# mosfet_ctl.net
KiCad netlist of a schematic drawn in EAGLE
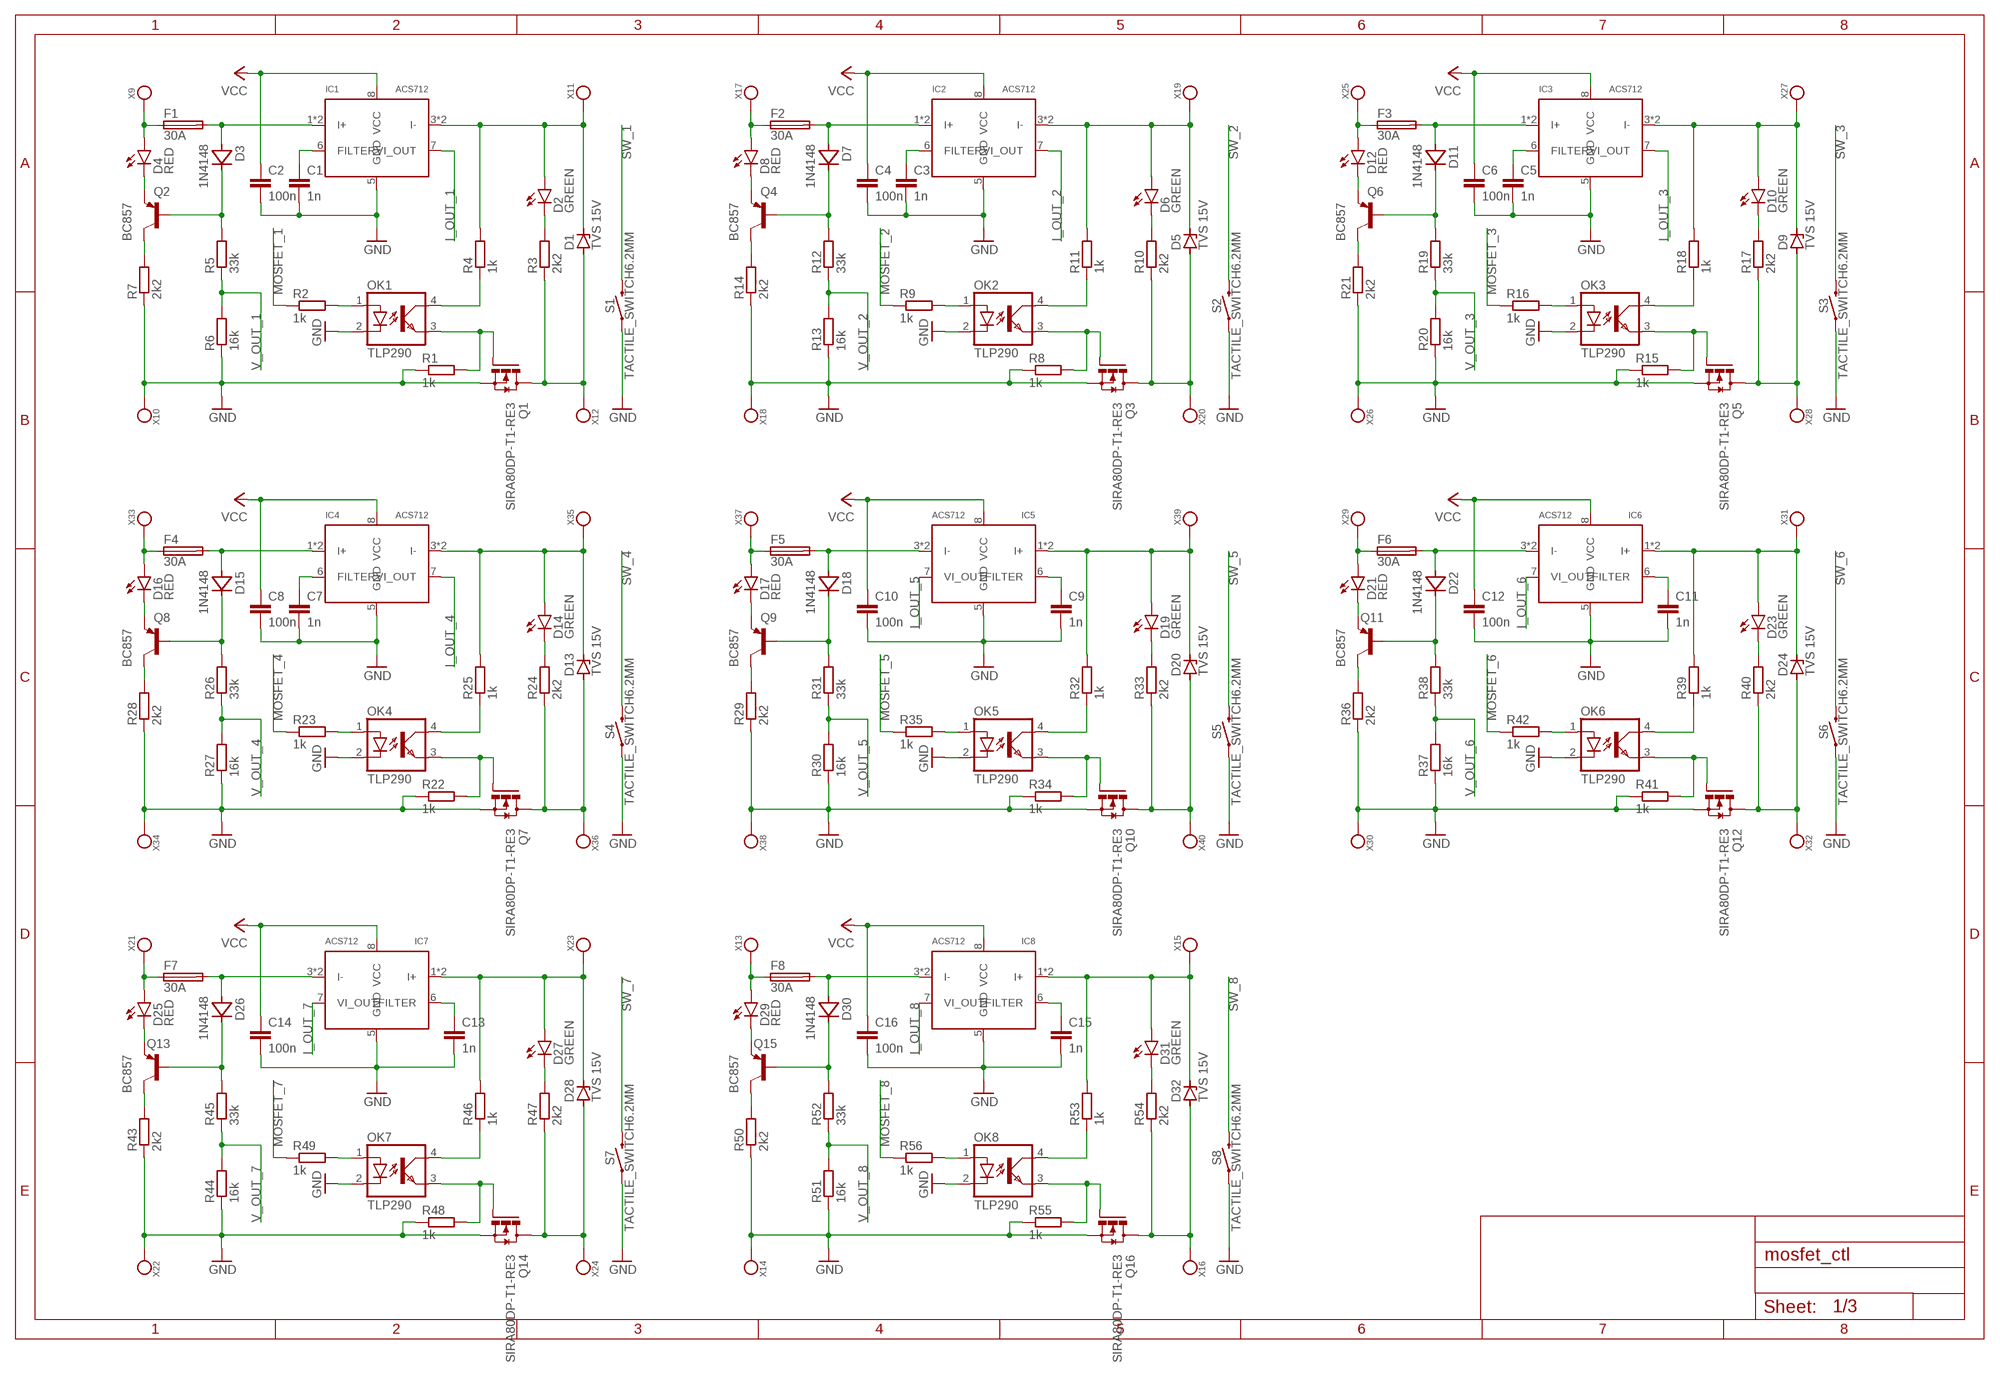
[diagram p0: schematic, sheet 1]
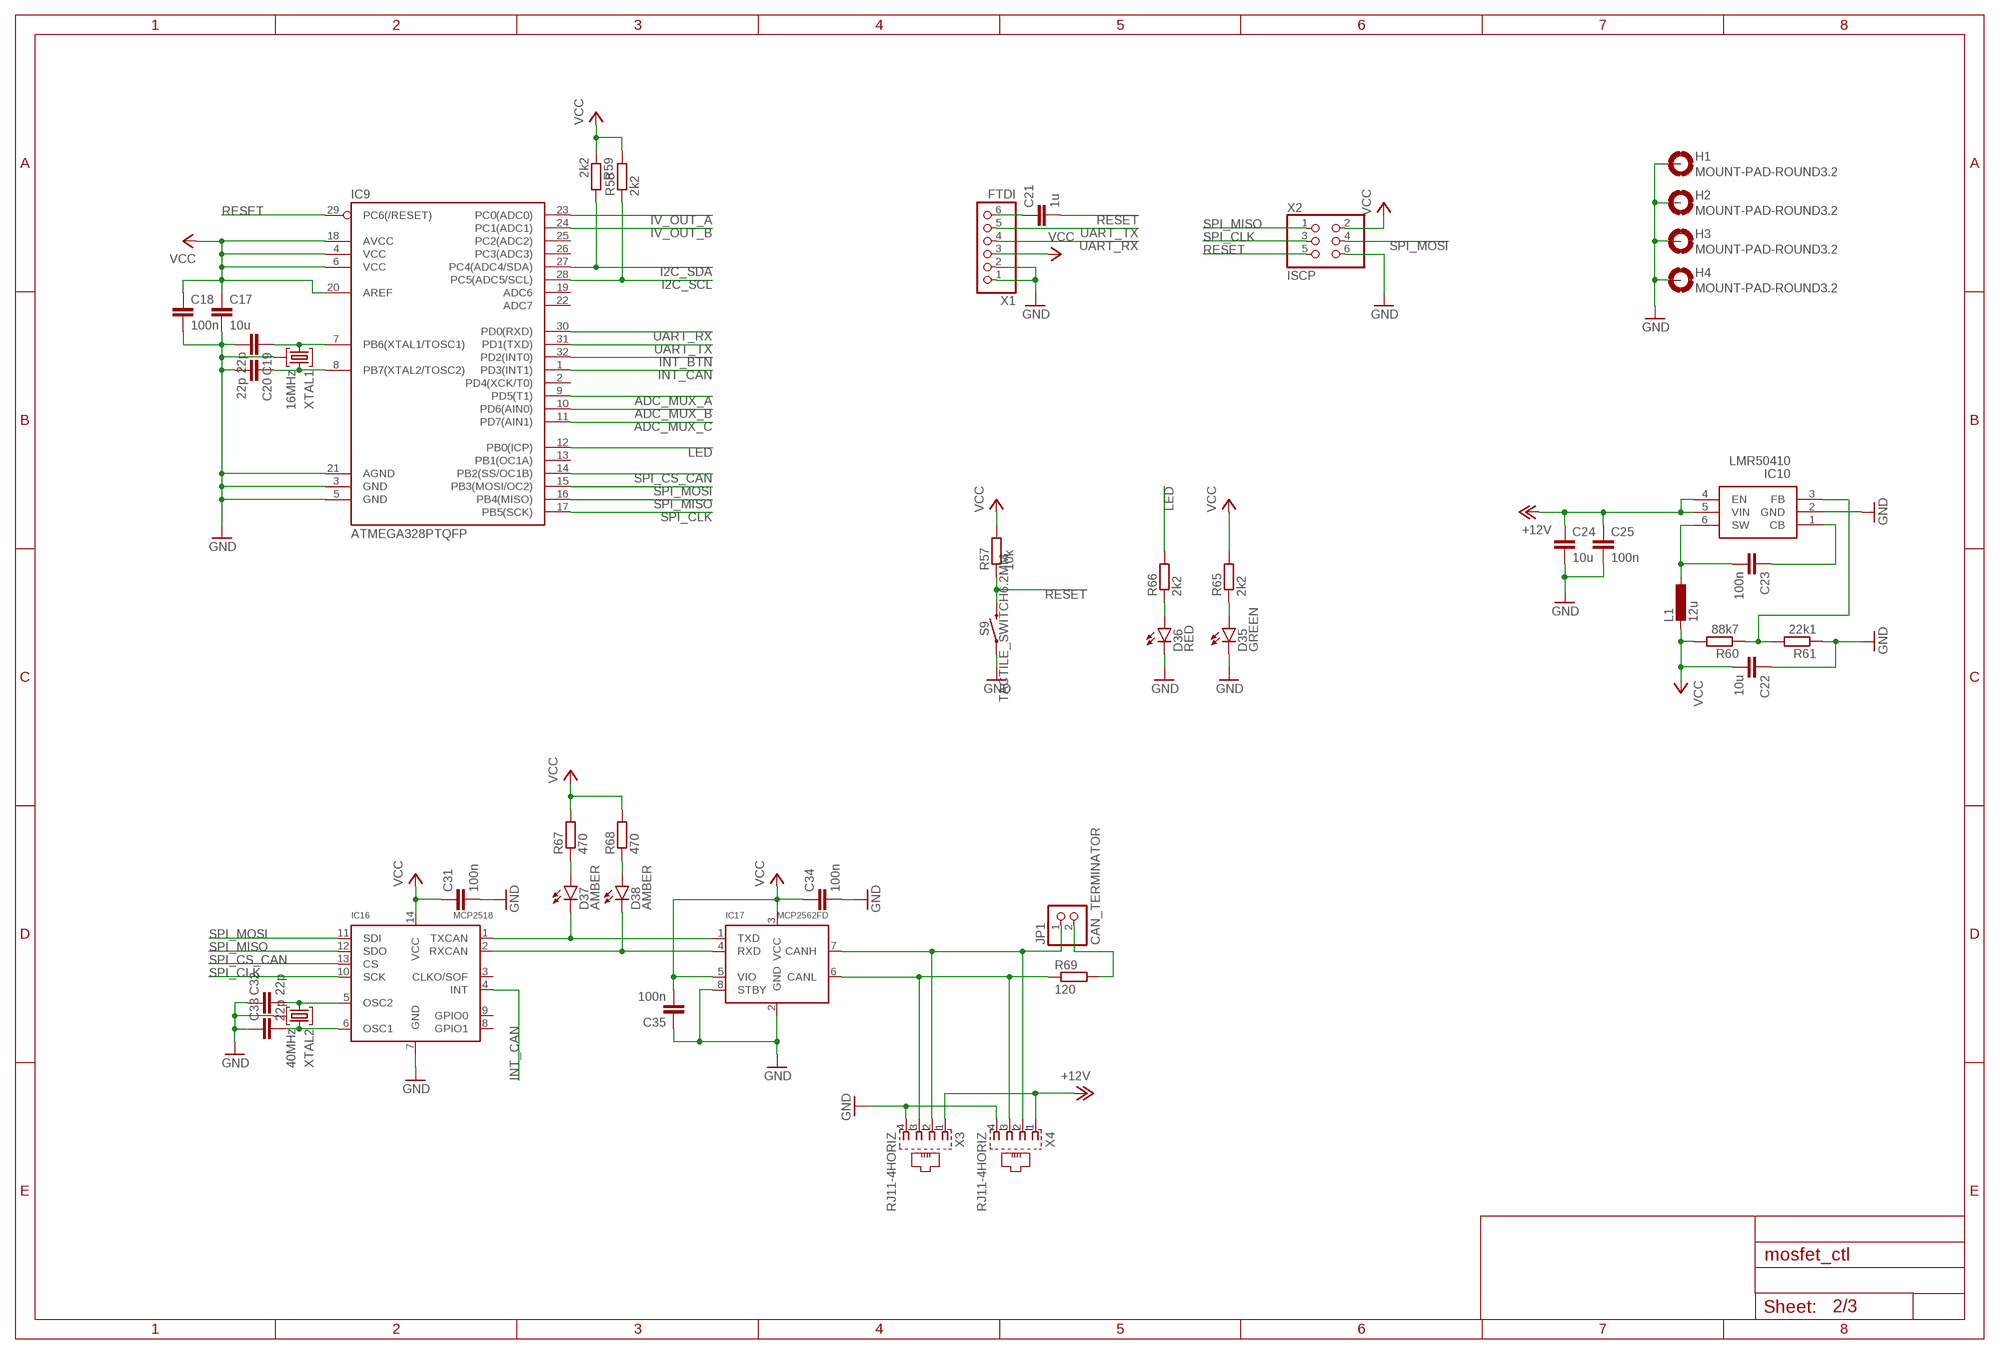
[diagram p1: schematic, sheet 2]
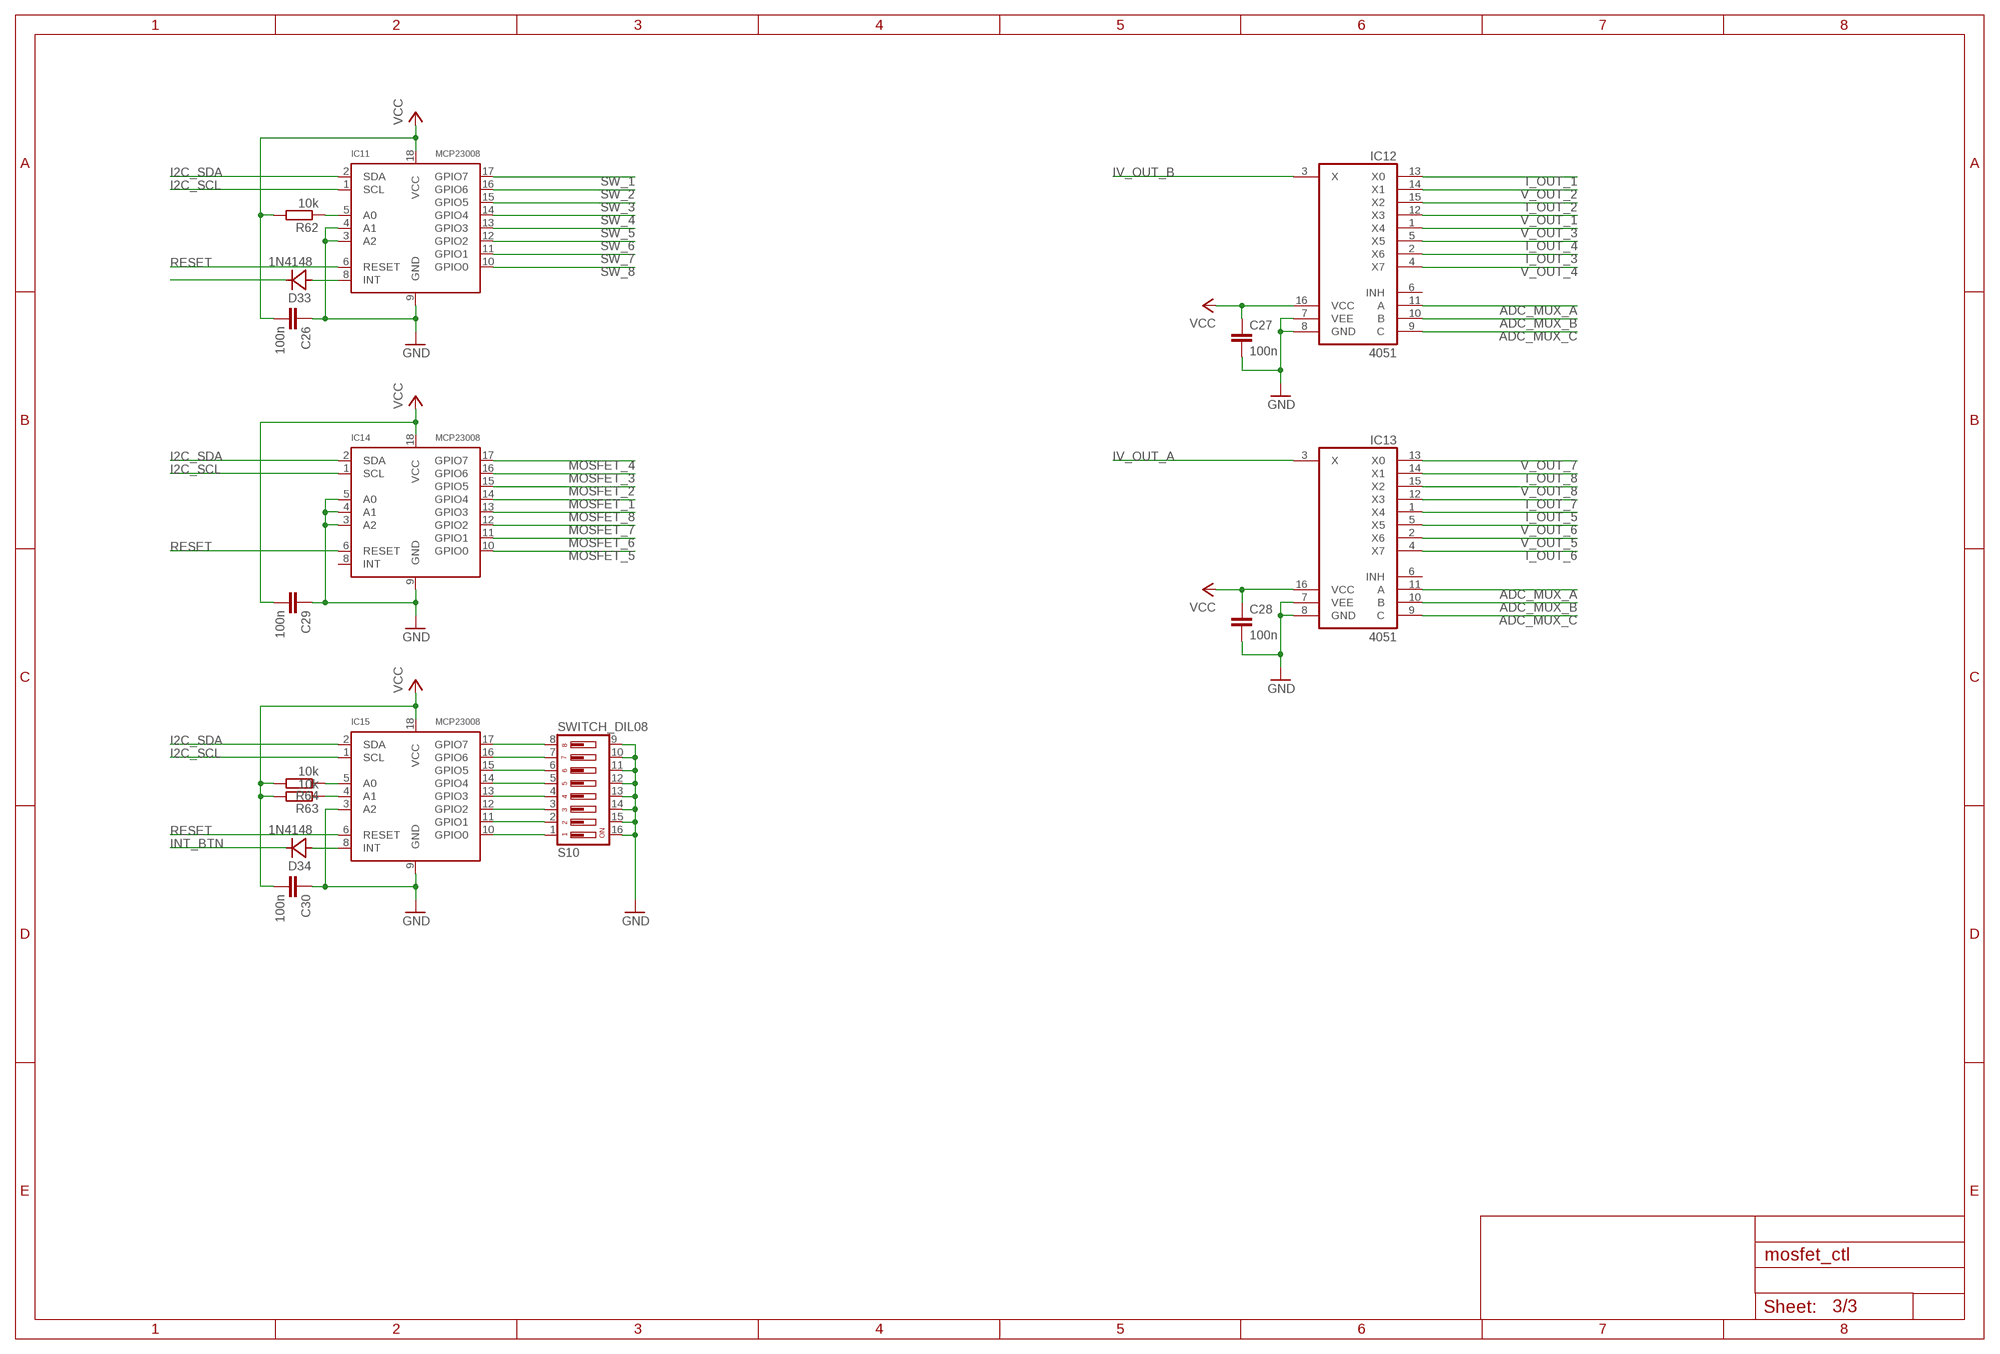
[diagram p2: schematic, sheet 3]

(export (version "E")
  (design (tool "Eeschema 10.0.6"))
  (components
    (comp (ref "C1")
      (value "1n")
      (footprint "eagle-import:C0805")
      (libsource (lib "eagle-import") (part "CAPACITOR0805"))
    )
    (comp (ref "C2")
      (value "100n")
      (footprint "eagle-import:C0805")
      (libsource (lib "eagle-import") (part "CAPACITOR0805"))
    )
    (comp (ref "C3")
      (value "1n")
      (footprint "eagle-import:C0805")
      (libsource (lib "eagle-import") (part "CAPACITOR0805"))
    )
    (comp (ref "C4")
      (value "100n")
      (footprint "eagle-import:C0805")
      (libsource (lib "eagle-import") (part "CAPACITOR0805"))
    )
    (comp (ref "C5")
      (value "1n")
      (footprint "eagle-import:C0805")
      (libsource (lib "eagle-import") (part "CAPACITOR0805"))
    )
    (comp (ref "C6")
      (value "100n")
      (footprint "eagle-import:C0805")
      (libsource (lib "eagle-import") (part "CAPACITOR0805"))
    )
    (comp (ref "C7")
      (value "1n")
      (footprint "eagle-import:C0805")
      (libsource (lib "eagle-import") (part "CAPACITOR0805"))
    )
    (comp (ref "C8")
      (value "100n")
      (footprint "eagle-import:C0805")
      (libsource (lib "eagle-import") (part "CAPACITOR0805"))
    )
    (comp (ref "C9")
      (value "1n")
      (footprint "eagle-import:C0805")
      (libsource (lib "eagle-import") (part "CAPACITOR0805"))
    )
    (comp (ref "C10")
      (value "100n")
      (footprint "eagle-import:C0805")
      (libsource (lib "eagle-import") (part "CAPACITOR0805"))
    )
    (comp (ref "C11")
      (value "1n")
      (footprint "eagle-import:C0805")
      (libsource (lib "eagle-import") (part "CAPACITOR0805"))
    )
    (comp (ref "C12")
      (value "100n")
      (footprint "eagle-import:C0805")
      (libsource (lib "eagle-import") (part "CAPACITOR0805"))
    )
    (comp (ref "C13")
      (value "1n")
      (footprint "eagle-import:C0805")
      (libsource (lib "eagle-import") (part "CAPACITOR0805"))
    )
    (comp (ref "C14")
      (value "100n")
      (footprint "eagle-import:C0805")
      (libsource (lib "eagle-import") (part "CAPACITOR0805"))
    )
    (comp (ref "C15")
      (value "1n")
      (footprint "eagle-import:C0805")
      (libsource (lib "eagle-import") (part "CAPACITOR0805"))
    )
    (comp (ref "C16")
      (value "100n")
      (footprint "eagle-import:C0805")
      (libsource (lib "eagle-import") (part "CAPACITOR0805"))
    )
    (comp (ref "D1")
      (value "TVS 15V")
      (footprint "eagle-import:DO214AC")
      (libsource (lib "eagle-import") (part "DIODE_ZENERDO-214AC"))
    )
    (comp (ref "D2")
      (value "GREEN")
      (footprint "eagle-import:CHIPLED_1206")
      (libsource (lib "eagle-import") (part "LED1206"))
    )
    (comp (ref "D3")
      (value "1N4148")
      (footprint "eagle-import:SOD123")
      (libsource (lib "eagle-import") (part "DIODESOD-123"))
    )
    (comp (ref "D4")
      (value "RED")
      (footprint "eagle-import:CHIPLED_1206")
      (libsource (lib "eagle-import") (part "LED1206"))
    )
    (comp (ref "D5")
      (value "TVS 15V")
      (footprint "eagle-import:DO214AC")
      (libsource (lib "eagle-import") (part "DIODE_ZENERDO-214AC"))
    )
    (comp (ref "D6")
      (value "GREEN")
      (footprint "eagle-import:CHIPLED_1206")
      (libsource (lib "eagle-import") (part "LED1206"))
    )
    (comp (ref "D7")
      (value "1N4148")
      (footprint "eagle-import:SOD123")
      (libsource (lib "eagle-import") (part "DIODESOD-123"))
    )
    (comp (ref "D8")
      (value "RED")
      (footprint "eagle-import:CHIPLED_1206")
      (libsource (lib "eagle-import") (part "LED1206"))
    )
    (comp (ref "D9")
      (value "TVS 15V")
      (footprint "eagle-import:DO214AC")
      (libsource (lib "eagle-import") (part "DIODE_ZENERDO-214AC"))
    )
    (comp (ref "D10")
      (value "GREEN")
      (footprint "eagle-import:CHIPLED_1206")
      (libsource (lib "eagle-import") (part "LED1206"))
    )
    (comp (ref "D11")
      (value "1N4148")
      (footprint "eagle-import:SOD123")
      (libsource (lib "eagle-import") (part "DIODESOD-123"))
    )
    (comp (ref "D12")
      (value "RED")
      (footprint "eagle-import:CHIPLED_1206")
      (libsource (lib "eagle-import") (part "LED1206"))
    )
    (comp (ref "D13")
      (value "TVS 15V")
      (footprint "eagle-import:DO214AC")
      (libsource (lib "eagle-import") (part "DIODE_ZENERDO-214AC"))
    )
    (comp (ref "D14")
      (value "GREEN")
      (footprint "eagle-import:CHIPLED_1206")
      (libsource (lib "eagle-import") (part "LED1206"))
    )
    (comp (ref "D15")
      (value "1N4148")
      (footprint "eagle-import:SOD123")
      (libsource (lib "eagle-import") (part "DIODESOD-123"))
    )
    (comp (ref "D16")
      (value "RED")
      (footprint "eagle-import:CHIPLED_1206")
      (libsource (lib "eagle-import") (part "LED1206"))
    )
    (comp (ref "D17")
      (value "RED")
      (footprint "eagle-import:CHIPLED_1206")
      (libsource (lib "eagle-import") (part "LED1206"))
    )
    (comp (ref "D18")
      (value "1N4148")
      (footprint "eagle-import:SOD123")
      (libsource (lib "eagle-import") (part "DIODESOD-123"))
    )
    (comp (ref "D19")
      (value "GREEN")
      (footprint "eagle-import:CHIPLED_1206")
      (libsource (lib "eagle-import") (part "LED1206"))
    )
    (comp (ref "D20")
      (value "TVS 15V")
      (footprint "eagle-import:DO214AC")
      (libsource (lib "eagle-import") (part "DIODE_ZENERDO-214AC"))
    )
    (comp (ref "D21")
      (value "RED")
      (footprint "eagle-import:CHIPLED_1206")
      (libsource (lib "eagle-import") (part "LED1206"))
    )
    (comp (ref "D22")
      (value "1N4148")
      (footprint "eagle-import:SOD123")
      (libsource (lib "eagle-import") (part "DIODESOD-123"))
    )
    (comp (ref "D23")
      (value "GREEN")
      (footprint "eagle-import:CHIPLED_1206")
      (libsource (lib "eagle-import") (part "LED1206"))
    )
    (comp (ref "D24")
      (value "TVS 15V")
      (footprint "eagle-import:DO214AC")
      (libsource (lib "eagle-import") (part "DIODE_ZENERDO-214AC"))
    )
    (comp (ref "D25")
      (value "RED")
      (footprint "eagle-import:CHIPLED_1206")
      (libsource (lib "eagle-import") (part "LED1206"))
    )
    (comp (ref "D26")
      (value "1N4148")
      (footprint "eagle-import:SOD123")
      (libsource (lib "eagle-import") (part "DIODESOD-123"))
    )
    (comp (ref "D27")
      (value "GREEN")
      (footprint "eagle-import:CHIPLED_1206")
      (libsource (lib "eagle-import") (part "LED1206"))
    )
    (comp (ref "D28")
      (value "TVS 15V")
      (footprint "eagle-import:DO214AC")
      (libsource (lib "eagle-import") (part "DIODE_ZENERDO-214AC"))
    )
    (comp (ref "D29")
      (value "RED")
      (footprint "eagle-import:CHIPLED_1206")
      (libsource (lib "eagle-import") (part "LED1206"))
    )
    (comp (ref "D30")
      (value "1N4148")
      (footprint "eagle-import:SOD123")
      (libsource (lib "eagle-import") (part "DIODESOD-123"))
    )
    (comp (ref "D31")
      (value "GREEN")
      (footprint "eagle-import:CHIPLED_1206")
      (libsource (lib "eagle-import") (part "LED1206"))
    )
    (comp (ref "D32")
      (value "TVS 15V")
      (footprint "eagle-import:DO214AC")
      (libsource (lib "eagle-import") (part "DIODE_ZENERDO-214AC"))
    )
    (comp (ref "F1")
      (value "30A")
      (footprint "eagle-import:KEYSTONE_3557-2")
      (libsource (lib "eagle-import") (part "KEYSTONE-3557-2"))
    )
    (comp (ref "F2")
      (value "30A")
      (footprint "eagle-import:KEYSTONE_3557-2")
      (libsource (lib "eagle-import") (part "KEYSTONE-3557-2"))
    )
    (comp (ref "F3")
      (value "30A")
      (footprint "eagle-import:KEYSTONE_3557-2")
      (libsource (lib "eagle-import") (part "KEYSTONE-3557-2"))
    )
    (comp (ref "F4")
      (value "30A")
      (footprint "eagle-import:KEYSTONE_3557-2")
      (libsource (lib "eagle-import") (part "KEYSTONE-3557-2"))
    )
    (comp (ref "F5")
      (value "30A")
      (footprint "eagle-import:KEYSTONE_3557-2")
      (libsource (lib "eagle-import") (part "KEYSTONE-3557-2"))
    )
    (comp (ref "F6")
      (value "30A")
      (footprint "eagle-import:KEYSTONE_3557-2")
      (libsource (lib "eagle-import") (part "KEYSTONE-3557-2"))
    )
    (comp (ref "F7")
      (value "30A")
      (footprint "eagle-import:KEYSTONE_3557-2")
      (libsource (lib "eagle-import") (part "KEYSTONE-3557-2"))
    )
    (comp (ref "F8")
      (value "30A")
      (footprint "eagle-import:KEYSTONE_3557-2")
      (libsource (lib "eagle-import") (part "KEYSTONE-3557-2"))
    )
    (comp (ref "IC1")
      (value "ACS712")
      (footprint "eagle-import:SO08")
      (libsource (lib "eagle-import") (part "ACS712"))
    )
    (comp (ref "IC2")
      (value "ACS712")
      (footprint "eagle-import:SO08")
      (libsource (lib "eagle-import") (part "ACS712"))
    )
    (comp (ref "IC3")
      (value "ACS712")
      (footprint "eagle-import:SO08")
      (libsource (lib "eagle-import") (part "ACS712"))
    )
    (comp (ref "IC4")
      (value "ACS712")
      (footprint "eagle-import:SO08")
      (libsource (lib "eagle-import") (part "ACS712"))
    )
    (comp (ref "IC5")
      (value "ACS712")
      (footprint "eagle-import:SO08")
      (libsource (lib "eagle-import") (part "ACS712"))
    )
    (comp (ref "IC6")
      (value "ACS712")
      (footprint "eagle-import:SO08")
      (libsource (lib "eagle-import") (part "ACS712"))
    )
    (comp (ref "IC7")
      (value "ACS712")
      (footprint "eagle-import:SO08")
      (libsource (lib "eagle-import") (part "ACS712"))
    )
    (comp (ref "IC8")
      (value "ACS712")
      (footprint "eagle-import:SO08")
      (libsource (lib "eagle-import") (part "ACS712"))
    )
    (comp (ref "OK1")
      (value "TLP290")
      (footprint "eagle-import:SO04")
      (libsource (lib "eagle-import") (part "OPTOCOUPLERSO4"))
    )
    (comp (ref "OK2")
      (value "TLP290")
      (footprint "eagle-import:SO04")
      (libsource (lib "eagle-import") (part "OPTOCOUPLERSO4"))
    )
    (comp (ref "OK3")
      (value "TLP290")
      (footprint "eagle-import:SO04")
      (libsource (lib "eagle-import") (part "OPTOCOUPLERSO4"))
    )
    (comp (ref "OK4")
      (value "TLP290")
      (footprint "eagle-import:SO04")
      (libsource (lib "eagle-import") (part "OPTOCOUPLERSO4"))
    )
    (comp (ref "OK5")
      (value "TLP290")
      (footprint "eagle-import:SO04")
      (libsource (lib "eagle-import") (part "OPTOCOUPLERSO4"))
    )
    (comp (ref "OK6")
      (value "TLP290")
      (footprint "eagle-import:SO04")
      (libsource (lib "eagle-import") (part "OPTOCOUPLERSO4"))
    )
    (comp (ref "OK7")
      (value "TLP290")
      (footprint "eagle-import:SO04")
      (libsource (lib "eagle-import") (part "OPTOCOUPLERSO4"))
    )
    (comp (ref "OK8")
      (value "TLP290")
      (footprint "eagle-import:SO04")
      (libsource (lib "eagle-import") (part "OPTOCOUPLERSO4"))
    )
    (comp (ref "Q1")
      (value "SIRA80DP-T1-RE3")
      (footprint "eagle-import:POWERPAK-SO8")
      (libsource (lib "eagle-import") (part "MOSFET_N_CHANNELPPAKSO8"))
    )
    (comp (ref "Q2")
      (value "BC857")
      (footprint "eagle-import:SOT23")
      (libsource (lib "eagle-import") (part "TRANSISTOR_PNPSOT23-CBE"))
    )
    (comp (ref "Q3")
      (value "SIRA80DP-T1-RE3")
      (footprint "eagle-import:POWERPAK-SO8")
      (libsource (lib "eagle-import") (part "MOSFET_N_CHANNELPPAKSO8"))
    )
    (comp (ref "Q4")
      (value "BC857")
      (footprint "eagle-import:SOT23")
      (libsource (lib "eagle-import") (part "TRANSISTOR_PNPSOT23-CBE"))
    )
    (comp (ref "Q5")
      (value "SIRA80DP-T1-RE3")
      (footprint "eagle-import:POWERPAK-SO8")
      (libsource (lib "eagle-import") (part "MOSFET_N_CHANNELPPAKSO8"))
    )
    (comp (ref "Q6")
      (value "BC857")
      (footprint "eagle-import:SOT23")
      (libsource (lib "eagle-import") (part "TRANSISTOR_PNPSOT23-CBE"))
    )
    (comp (ref "Q7")
      (value "SIRA80DP-T1-RE3")
      (footprint "eagle-import:POWERPAK-SO8")
      (libsource (lib "eagle-import") (part "MOSFET_N_CHANNELPPAKSO8"))
    )
    (comp (ref "Q8")
      (value "BC857")
      (footprint "eagle-import:SOT23")
      (libsource (lib "eagle-import") (part "TRANSISTOR_PNPSOT23-CBE"))
    )
    (comp (ref "Q9")
      (value "BC857")
      (footprint "eagle-import:SOT23")
      (libsource (lib "eagle-import") (part "TRANSISTOR_PNPSOT23-CBE"))
    )
    (comp (ref "Q10")
      (value "SIRA80DP-T1-RE3")
      (footprint "eagle-import:POWERPAK-SO8")
      (libsource (lib "eagle-import") (part "MOSFET_N_CHANNELPPAKSO8"))
    )
    (comp (ref "Q11")
      (value "BC857")
      (footprint "eagle-import:SOT23")
      (libsource (lib "eagle-import") (part "TRANSISTOR_PNPSOT23-CBE"))
    )
    (comp (ref "Q12")
      (value "SIRA80DP-T1-RE3")
      (footprint "eagle-import:POWERPAK-SO8")
      (libsource (lib "eagle-import") (part "MOSFET_N_CHANNELPPAKSO8"))
    )
    (comp (ref "Q13")
      (value "BC857")
      (footprint "eagle-import:SOT23")
      (libsource (lib "eagle-import") (part "TRANSISTOR_PNPSOT23-CBE"))
    )
    (comp (ref "Q14")
      (value "SIRA80DP-T1-RE3")
      (footprint "eagle-import:POWERPAK-SO8")
      (libsource (lib "eagle-import") (part "MOSFET_N_CHANNELPPAKSO8"))
    )
    (comp (ref "Q15")
      (value "BC857")
      (footprint "eagle-import:SOT23")
      (libsource (lib "eagle-import") (part "TRANSISTOR_PNPSOT23-CBE"))
    )
    (comp (ref "Q16")
      (value "SIRA80DP-T1-RE3")
      (footprint "eagle-import:POWERPAK-SO8")
      (libsource (lib "eagle-import") (part "MOSFET_N_CHANNELPPAKSO8"))
    )
    (comp (ref "R1")
      (value "1k")
      (footprint "eagle-import:R0805")
      (libsource (lib "eagle-import") (part "RESISTOR0805"))
    )
    (comp (ref "R2")
      (value "1k")
      (footprint "eagle-import:R0805")
      (libsource (lib "eagle-import") (part "RESISTOR0805"))
    )
    (comp (ref "R3")
      (value "2k2")
      (footprint "eagle-import:R0805")
      (libsource (lib "eagle-import") (part "RESISTOR0805"))
    )
    (comp (ref "R4")
      (value "1k")
      (footprint "eagle-import:R0805")
      (libsource (lib "eagle-import") (part "RESISTOR0805"))
    )
    (comp (ref "R5")
      (value "33k")
      (footprint "eagle-import:R0805")
      (libsource (lib "eagle-import") (part "RESISTOR0805"))
    )
    (comp (ref "R6")
      (value "16k")
      (footprint "eagle-import:R0805")
      (libsource (lib "eagle-import") (part "RESISTOR0805"))
    )
    (comp (ref "R7")
      (value "2k2")
      (footprint "eagle-import:R0805")
      (libsource (lib "eagle-import") (part "RESISTOR0805"))
    )
    (comp (ref "R8")
      (value "1k")
      (footprint "eagle-import:R0805")
      (libsource (lib "eagle-import") (part "RESISTOR0805"))
    )
    (comp (ref "R9")
      (value "1k")
      (footprint "eagle-import:R0805")
      (libsource (lib "eagle-import") (part "RESISTOR0805"))
    )
    (comp (ref "R10")
      (value "2k2")
      (footprint "eagle-import:R0805")
      (libsource (lib "eagle-import") (part "RESISTOR0805"))
    )
    (comp (ref "R11")
      (value "1k")
      (footprint "eagle-import:R0805")
      (libsource (lib "eagle-import") (part "RESISTOR0805"))
    )
    (comp (ref "R12")
      (value "33k")
      (footprint "eagle-import:R0805")
      (libsource (lib "eagle-import") (part "RESISTOR0805"))
    )
    (comp (ref "R13")
      (value "16k")
      (footprint "eagle-import:R0805")
      (libsource (lib "eagle-import") (part "RESISTOR0805"))
    )
    (comp (ref "R14")
      (value "2k2")
      (footprint "eagle-import:R0805")
      (libsource (lib "eagle-import") (part "RESISTOR0805"))
    )
    (comp (ref "R15")
      (value "1k")
      (footprint "eagle-import:R0805")
      (libsource (lib "eagle-import") (part "RESISTOR0805"))
    )
    (comp (ref "R16")
      (value "1k")
      (footprint "eagle-import:R0805")
      (libsource (lib "eagle-import") (part "RESISTOR0805"))
    )
    (comp (ref "R17")
      (value "2k2")
      (footprint "eagle-import:R0805")
      (libsource (lib "eagle-import") (part "RESISTOR0805"))
    )
    (comp (ref "R18")
      (value "1k")
      (footprint "eagle-import:R0805")
      (libsource (lib "eagle-import") (part "RESISTOR0805"))
    )
    (comp (ref "R19")
      (value "33k")
      (footprint "eagle-import:R0805")
      (libsource (lib "eagle-import") (part "RESISTOR0805"))
    )
    (comp (ref "R20")
      (value "16k")
      (footprint "eagle-import:R0805")
      (libsource (lib "eagle-import") (part "RESISTOR0805"))
    )
    (comp (ref "R21")
      (value "2k2")
      (footprint "eagle-import:R0805")
      (libsource (lib "eagle-import") (part "RESISTOR0805"))
    )
    (comp (ref "R22")
      (value "1k")
      (footprint "eagle-import:R0805")
      (libsource (lib "eagle-import") (part "RESISTOR0805"))
    )
    (comp (ref "R23")
      (value "1k")
      (footprint "eagle-import:R0805")
      (libsource (lib "eagle-import") (part "RESISTOR0805"))
    )
    (comp (ref "R24")
      (value "2k2")
      (footprint "eagle-import:R0805")
      (libsource (lib "eagle-import") (part "RESISTOR0805"))
    )
    (comp (ref "R25")
      (value "1k")
      (footprint "eagle-import:R0805")
      (libsource (lib "eagle-import") (part "RESISTOR0805"))
    )
    (comp (ref "R26")
      (value "33k")
      (footprint "eagle-import:R0805")
      (libsource (lib "eagle-import") (part "RESISTOR0805"))
    )
    (comp (ref "R27")
      (value "16k")
      (footprint "eagle-import:R0805")
      (libsource (lib "eagle-import") (part "RESISTOR0805"))
    )
    (comp (ref "R28")
      (value "2k2")
      (footprint "eagle-import:R0805")
      (libsource (lib "eagle-import") (part "RESISTOR0805"))
    )
    (comp (ref "R29")
      (value "2k2")
      (footprint "eagle-import:R0805")
      (libsource (lib "eagle-import") (part "RESISTOR0805"))
    )
    (comp (ref "R30")
      (value "16k")
      (footprint "eagle-import:R0805")
      (libsource (lib "eagle-import") (part "RESISTOR0805"))
    )
    (comp (ref "R31")
      (value "33k")
      (footprint "eagle-import:R0805")
      (libsource (lib "eagle-import") (part "RESISTOR0805"))
    )
    (comp (ref "R32")
      (value "1k")
      (footprint "eagle-import:R0805")
      (libsource (lib "eagle-import") (part "RESISTOR0805"))
    )
    (comp (ref "R33")
      (value "2k2")
      (footprint "eagle-import:R0805")
      (libsource (lib "eagle-import") (part "RESISTOR0805"))
    )
    (comp (ref "R34")
      (value "1k")
      (footprint "eagle-import:R0805")
      (libsource (lib "eagle-import") (part "RESISTOR0805"))
    )
    (comp (ref "R35")
      (value "1k")
      (footprint "eagle-import:R0805")
      (libsource (lib "eagle-import") (part "RESISTOR0805"))
    )
    (comp (ref "R36")
      (value "2k2")
      (footprint "eagle-import:R0805")
      (libsource (lib "eagle-import") (part "RESISTOR0805"))
    )
    (comp (ref "R37")
      (value "16k")
      (footprint "eagle-import:R0805")
      (libsource (lib "eagle-import") (part "RESISTOR0805"))
    )
    (comp (ref "R38")
      (value "33k")
      (footprint "eagle-import:R0805")
      (libsource (lib "eagle-import") (part "RESISTOR0805"))
    )
    (comp (ref "R39")
      (value "1k")
      (footprint "eagle-import:R0805")
      (libsource (lib "eagle-import") (part "RESISTOR0805"))
    )
    (comp (ref "R40")
      (value "2k2")
      (footprint "eagle-import:R0805")
      (libsource (lib "eagle-import") (part "RESISTOR0805"))
    )
    (comp (ref "R41")
      (value "1k")
      (footprint "eagle-import:R0805")
      (libsource (lib "eagle-import") (part "RESISTOR0805"))
    )
    (comp (ref "R42")
      (value "1k")
      (footprint "eagle-import:R0805")
      (libsource (lib "eagle-import") (part "RESISTOR0805"))
    )
    (comp (ref "R43")
      (value "2k2")
      (footprint "eagle-import:R0805")
      (libsource (lib "eagle-import") (part "RESISTOR0805"))
    )
    (comp (ref "R44")
      (value "16k")
      (footprint "eagle-import:R0805")
      (libsource (lib "eagle-import") (part "RESISTOR0805"))
    )
    (comp (ref "R45")
      (value "33k")
      (footprint "eagle-import:R0805")
      (libsource (lib "eagle-import") (part "RESISTOR0805"))
    )
    (comp (ref "R46")
      (value "1k")
      (footprint "eagle-import:R0805")
      (libsource (lib "eagle-import") (part "RESISTOR0805"))
    )
    (comp (ref "R47")
      (value "2k2")
      (footprint "eagle-import:R0805")
      (libsource (lib "eagle-import") (part "RESISTOR0805"))
    )
    (comp (ref "R48")
      (value "1k")
      (footprint "eagle-import:R0805")
      (libsource (lib "eagle-import") (part "RESISTOR0805"))
    )
    (comp (ref "R49")
      (value "1k")
      (footprint "eagle-import:R0805")
      (libsource (lib "eagle-import") (part "RESISTOR0805"))
    )
    (comp (ref "R50")
      (value "2k2")
      (footprint "eagle-import:R0805")
      (libsource (lib "eagle-import") (part "RESISTOR0805"))
    )
    (comp (ref "R51")
      (value "16k")
      (footprint "eagle-import:R0805")
      (libsource (lib "eagle-import") (part "RESISTOR0805"))
    )
    (comp (ref "R52")
      (value "33k")
      (footprint "eagle-import:R0805")
      (libsource (lib "eagle-import") (part "RESISTOR0805"))
    )
    (comp (ref "R53")
      (value "1k")
      (footprint "eagle-import:R0805")
      (libsource (lib "eagle-import") (part "RESISTOR0805"))
    )
    (comp (ref "R54")
      (value "2k2")
      (footprint "eagle-import:R0805")
      (libsource (lib "eagle-import") (part "RESISTOR0805"))
    )
    (comp (ref "R55")
      (value "1k")
      (footprint "eagle-import:R0805")
      (libsource (lib "eagle-import") (part "RESISTOR0805"))
    )
    (comp (ref "R56")
      (value "1k")
      (footprint "eagle-import:R0805")
      (libsource (lib "eagle-import") (part "RESISTOR0805"))
    )
    (comp (ref "S1")
      (value "TACTILE_SWITCH6.2MM")
      (footprint "eagle-import:TACTILE_SWITCH_SMD_6.2MM")
      (libsource (lib "eagle-import") (part "TACTILE_SWITCH6.2MM"))
    )
    (comp (ref "S2")
      (value "TACTILE_SWITCH6.2MM")
      (footprint "eagle-import:TACTILE_SWITCH_SMD_6.2MM")
      (libsource (lib "eagle-import") (part "TACTILE_SWITCH6.2MM"))
    )
    (comp (ref "S3")
      (value "TACTILE_SWITCH6.2MM")
      (footprint "eagle-import:TACTILE_SWITCH_SMD_6.2MM")
      (libsource (lib "eagle-import") (part "TACTILE_SWITCH6.2MM"))
    )
    (comp (ref "S4")
      (value "TACTILE_SWITCH6.2MM")
      (footprint "eagle-import:TACTILE_SWITCH_SMD_6.2MM")
      (libsource (lib "eagle-import") (part "TACTILE_SWITCH6.2MM"))
    )
    (comp (ref "S5")
      (value "TACTILE_SWITCH6.2MM")
      (footprint "eagle-import:TACTILE_SWITCH_SMD_6.2MM")
      (libsource (lib "eagle-import") (part "TACTILE_SWITCH6.2MM"))
    )
    (comp (ref "S6")
      (value "TACTILE_SWITCH6.2MM")
      (footprint "eagle-import:TACTILE_SWITCH_SMD_6.2MM")
      (libsource (lib "eagle-import") (part "TACTILE_SWITCH6.2MM"))
    )
    (comp (ref "S7")
      (value "TACTILE_SWITCH6.2MM")
      (footprint "eagle-import:TACTILE_SWITCH_SMD_6.2MM")
      (libsource (lib "eagle-import") (part "TACTILE_SWITCH6.2MM"))
    )
    (comp (ref "S8")
      (value "TACTILE_SWITCH6.2MM")
      (footprint "eagle-import:TACTILE_SWITCH_SMD_6.2MM")
      (libsource (lib "eagle-import") (part "TACTILE_SWITCH6.2MM"))
    )
    (comp (ref "X9")
      (value "KEYSTONE_7800")
      (footprint "eagle-import:KEYSTONE_7800")
      (libsource (lib "eagle-import") (part "KEYSTONE_7800"))
    )
    (comp (ref "X10")
      (value "KEYSTONE_7800")
      (footprint "eagle-import:KEYSTONE_7800")
      (libsource (lib "eagle-import") (part "KEYSTONE_7800"))
    )
    (comp (ref "X11")
      (value "KEYSTONE_7800")
      (footprint "eagle-import:KEYSTONE_7800")
      (libsource (lib "eagle-import") (part "KEYSTONE_7800"))
    )
    (comp (ref "X12")
      (value "KEYSTONE_7800")
      (footprint "eagle-import:KEYSTONE_7800")
      (libsource (lib "eagle-import") (part "KEYSTONE_7800"))
    )
    (comp (ref "X13")
      (value "KEYSTONE_7800")
      (footprint "eagle-import:KEYSTONE_7800")
      (libsource (lib "eagle-import") (part "KEYSTONE_7800"))
    )
    (comp (ref "X14")
      (value "KEYSTONE_7800")
      (footprint "eagle-import:KEYSTONE_7800")
      (libsource (lib "eagle-import") (part "KEYSTONE_7800"))
    )
    (comp (ref "X15")
      (value "KEYSTONE_7800")
      (footprint "eagle-import:KEYSTONE_7800")
      (libsource (lib "eagle-import") (part "KEYSTONE_7800"))
    )
    (comp (ref "X16")
      (value "KEYSTONE_7800")
      (footprint "eagle-import:KEYSTONE_7800")
      (libsource (lib "eagle-import") (part "KEYSTONE_7800"))
    )
    (comp (ref "X17")
      (value "KEYSTONE_7800")
      (footprint "eagle-import:KEYSTONE_7800")
      (libsource (lib "eagle-import") (part "KEYSTONE_7800"))
    )
    (comp (ref "X18")
      (value "KEYSTONE_7800")
      (footprint "eagle-import:KEYSTONE_7800")
      (libsource (lib "eagle-import") (part "KEYSTONE_7800"))
    )
    (comp (ref "X19")
      (value "KEYSTONE_7800")
      (footprint "eagle-import:KEYSTONE_7800")
      (libsource (lib "eagle-import") (part "KEYSTONE_7800"))
    )
    (comp (ref "X20")
      (value "KEYSTONE_7800")
      (footprint "eagle-import:KEYSTONE_7800")
      (libsource (lib "eagle-import") (part "KEYSTONE_7800"))
    )
    (comp (ref "X21")
      (value "KEYSTONE_7800")
      (footprint "eagle-import:KEYSTONE_7800")
      (libsource (lib "eagle-import") (part "KEYSTONE_7800"))
    )
    (comp (ref "X22")
      (value "KEYSTONE_7800")
      (footprint "eagle-import:KEYSTONE_7800")
      (libsource (lib "eagle-import") (part "KEYSTONE_7800"))
    )
    (comp (ref "X23")
      (value "KEYSTONE_7800")
      (footprint "eagle-import:KEYSTONE_7800")
      (libsource (lib "eagle-import") (part "KEYSTONE_7800"))
    )
    (comp (ref "X24")
      (value "KEYSTONE_7800")
      (footprint "eagle-import:KEYSTONE_7800")
      (libsource (lib "eagle-import") (part "KEYSTONE_7800"))
    )
    (comp (ref "X25")
      (value "KEYSTONE_7800")
      (footprint "eagle-import:KEYSTONE_7800")
      (libsource (lib "eagle-import") (part "KEYSTONE_7800"))
    )
    (comp (ref "X26")
      (value "KEYSTONE_7800")
      (footprint "eagle-import:KEYSTONE_7800")
      (libsource (lib "eagle-import") (part "KEYSTONE_7800"))
    )
    (comp (ref "X27")
      (value "KEYSTONE_7800")
      (footprint "eagle-import:KEYSTONE_7800")
      (libsource (lib "eagle-import") (part "KEYSTONE_7800"))
    )
    (comp (ref "X28")
      (value "KEYSTONE_7800")
      (footprint "eagle-import:KEYSTONE_7800")
      (libsource (lib "eagle-import") (part "KEYSTONE_7800"))
    )
    (comp (ref "X29")
      (value "KEYSTONE_7800")
      (footprint "eagle-import:KEYSTONE_7800")
      (libsource (lib "eagle-import") (part "KEYSTONE_7800"))
    )
    (comp (ref "X30")
      (value "KEYSTONE_7800")
      (footprint "eagle-import:KEYSTONE_7800")
      (libsource (lib "eagle-import") (part "KEYSTONE_7800"))
    )
    (comp (ref "X31")
      (value "KEYSTONE_7800")
      (footprint "eagle-import:KEYSTONE_7800")
      (libsource (lib "eagle-import") (part "KEYSTONE_7800"))
    )
    (comp (ref "X32")
      (value "KEYSTONE_7800")
      (footprint "eagle-import:KEYSTONE_7800")
      (libsource (lib "eagle-import") (part "KEYSTONE_7800"))
    )
    (comp (ref "X33")
      (value "KEYSTONE_7800")
      (footprint "eagle-import:KEYSTONE_7800")
      (libsource (lib "eagle-import") (part "KEYSTONE_7800"))
    )
    (comp (ref "X34")
      (value "KEYSTONE_7800")
      (footprint "eagle-import:KEYSTONE_7800")
      (libsource (lib "eagle-import") (part "KEYSTONE_7800"))
    )
    (comp (ref "X35")
      (value "KEYSTONE_7800")
      (footprint "eagle-import:KEYSTONE_7800")
      (libsource (lib "eagle-import") (part "KEYSTONE_7800"))
    )
    (comp (ref "X36")
      (value "KEYSTONE_7800")
      (footprint "eagle-import:KEYSTONE_7800")
      (libsource (lib "eagle-import") (part "KEYSTONE_7800"))
    )
    (comp (ref "X37")
      (value "KEYSTONE_7800")
      (footprint "eagle-import:KEYSTONE_7800")
      (libsource (lib "eagle-import") (part "KEYSTONE_7800"))
    )
    (comp (ref "X38")
      (value "KEYSTONE_7800")
      (footprint "eagle-import:KEYSTONE_7800")
      (libsource (lib "eagle-import") (part "KEYSTONE_7800"))
    )
    (comp (ref "X39")
      (value "KEYSTONE_7800")
      (footprint "eagle-import:KEYSTONE_7800")
      (libsource (lib "eagle-import") (part "KEYSTONE_7800"))
    )
    (comp (ref "X40")
      (value "KEYSTONE_7800")
      (footprint "eagle-import:KEYSTONE_7800")
      (libsource (lib "eagle-import") (part "KEYSTONE_7800"))
    )
    (comp (ref "C17")
      (value "10u")
      (footprint "eagle-import:C1206")
      (libsource (lib "eagle-import") (part "CAPACITOR1206"))
    )
    (comp (ref "C18")
      (value "100n")
      (footprint "eagle-import:C0805")
      (libsource (lib "eagle-import") (part "CAPACITOR0805"))
    )
    (comp (ref "C19")
      (value "22p")
      (footprint "eagle-import:C0805")
      (libsource (lib "eagle-import") (part "CAPACITOR0805"))
    )
    (comp (ref "C20")
      (value "22p")
      (footprint "eagle-import:C0805")
      (libsource (lib "eagle-import") (part "CAPACITOR0805"))
    )
    (comp (ref "C21")
      (value "1u")
      (footprint "eagle-import:C0805")
      (libsource (lib "eagle-import") (part "CAPACITOR0805"))
    )
    (comp (ref "C22")
      (value "10u")
      (footprint "eagle-import:C1206")
      (libsource (lib "eagle-import") (part "CAPACITOR1206"))
    )
    (comp (ref "C23")
      (value "100n")
      (footprint "eagle-import:C0805")
      (libsource (lib "eagle-import") (part "CAPACITOR0805"))
    )
    (comp (ref "C24")
      (value "10u")
      (footprint "eagle-import:C1206")
      (libsource (lib "eagle-import") (part "CAPACITOR1206"))
    )
    (comp (ref "C25")
      (value "100n")
      (footprint "eagle-import:C0805")
      (libsource (lib "eagle-import") (part "CAPACITOR0805"))
    )
    (comp (ref "C31")
      (value "100n")
      (footprint "eagle-import:C0805")
      (libsource (lib "eagle-import") (part "CAPACITOR0805"))
    )
    (comp (ref "C32")
      (value "22p")
      (footprint "eagle-import:C0805")
      (libsource (lib "eagle-import") (part "CAPACITOR0805"))
    )
    (comp (ref "C33")
      (value "22p")
      (footprint "eagle-import:C0805")
      (libsource (lib "eagle-import") (part "CAPACITOR0805"))
    )
    (comp (ref "C34")
      (value "100n")
      (footprint "eagle-import:C0805")
      (libsource (lib "eagle-import") (part "CAPACITOR0805"))
    )
    (comp (ref "C35")
      (value "100n")
      (footprint "eagle-import:C0805")
      (libsource (lib "eagle-import") (part "CAPACITOR0805"))
    )
    (comp (ref "D35")
      (value "GREEN")
      (footprint "eagle-import:CHIPLED_1206")
      (libsource (lib "eagle-import") (part "LED1206"))
    )
    (comp (ref "D36")
      (value "RED")
      (footprint "eagle-import:CHIPLED_1206")
      (libsource (lib "eagle-import") (part "LED1206"))
    )
    (comp (ref "D37")
      (value "AMBER")
      (footprint "eagle-import:CHIPLED_1206")
      (libsource (lib "eagle-import") (part "LED1206"))
    )
    (comp (ref "D38")
      (value "AMBER")
      (footprint "eagle-import:CHIPLED_1206")
      (libsource (lib "eagle-import") (part "LED1206"))
    )
    (comp (ref "H1")
      (value "MOUNT-PAD-ROUND3.2")
      (footprint "eagle-import:3,2-PAD")
      (libsource (lib "eagle-import") (part "MOUNT-PAD-ROUND3.2"))
    )
    (comp (ref "H2")
      (value "MOUNT-PAD-ROUND3.2")
      (footprint "eagle-import:3,2-PAD")
      (libsource (lib "eagle-import") (part "MOUNT-PAD-ROUND3.2"))
    )
    (comp (ref "H3")
      (value "MOUNT-PAD-ROUND3.2")
      (footprint "eagle-import:3,2-PAD")
      (libsource (lib "eagle-import") (part "MOUNT-PAD-ROUND3.2"))
    )
    (comp (ref "H4")
      (value "MOUNT-PAD-ROUND3.2")
      (footprint "eagle-import:3,2-PAD")
      (libsource (lib "eagle-import") (part "MOUNT-PAD-ROUND3.2"))
    )
    (comp (ref "IC9")
      (value "ATMEGA328PTQFP")
      (footprint "eagle-import:TQFP32_0.8MM_7X7MM")
      (libsource (lib "eagle-import") (part "ATMEGA328PTQFP"))
    )
    (comp (ref "IC10")
      (value "LMR50410")
      (footprint "eagle-import:SOT23-6")
      (libsource (lib "eagle-import") (part "LMR50410"))
    )
    (comp (ref "IC16")
      (value "MCP2518")
      (footprint "eagle-import:SO14")
      (libsource (lib "eagle-import") (part "MCP2518FDSO14"))
    )
    (comp (ref "IC17")
      (value "MCP2562FD")
      (footprint "eagle-import:SO08")
      (libsource (lib "eagle-import") (part "MCP2562FDSO08"))
    )
    (comp (ref "JP1")
      (value "CAN_TERMINATOR")
      (footprint "eagle-import:1X02")
      (libsource (lib "eagle-import") (part "PINHD-1X2"))
    )
    (comp (ref "L1")
      (value "12u")
      (footprint "eagle-import:L_7.3MM")
      (libsource (lib "eagle-import") (part "INDUCTOR7.3MM"))
    )
    (comp (ref "R57")
      (value "10k")
      (footprint "eagle-import:R0805")
      (libsource (lib "eagle-import") (part "RESISTOR0805"))
    )
    (comp (ref "R58")
      (value "2k2")
      (footprint "eagle-import:R0805")
      (libsource (lib "eagle-import") (part "RESISTOR0805"))
    )
    (comp (ref "R59")
      (value "2k2")
      (footprint "eagle-import:R0805")
      (libsource (lib "eagle-import") (part "RESISTOR0805"))
    )
    (comp (ref "R60")
      (value "88k7")
      (footprint "eagle-import:R0805")
      (libsource (lib "eagle-import") (part "RESISTOR0805"))
    )
    (comp (ref "R61")
      (value "22k1")
      (footprint "eagle-import:R0805")
      (libsource (lib "eagle-import") (part "RESISTOR0805"))
    )
    (comp (ref "R65")
      (value "2k2")
      (footprint "eagle-import:R0805")
      (libsource (lib "eagle-import") (part "RESISTOR0805"))
    )
    (comp (ref "R66")
      (value "2k2")
      (footprint "eagle-import:R0805")
      (libsource (lib "eagle-import") (part "RESISTOR0805"))
    )
    (comp (ref "R67")
      (value "470")
      (footprint "eagle-import:R0805")
      (libsource (lib "eagle-import") (part "RESISTOR0805"))
    )
    (comp (ref "R68")
      (value "470")
      (footprint "eagle-import:R0805")
      (libsource (lib "eagle-import") (part "RESISTOR0805"))
    )
    (comp (ref "R69")
      (value "120")
      (footprint "eagle-import:R0805")
      (libsource (lib "eagle-import") (part "RESISTOR0805"))
    )
    (comp (ref "S9")
      (value "TACTILE_SWITCH6.2MM")
      (footprint "eagle-import:TACTILE_SWITCH_SMD_6.2MM")
      (libsource (lib "eagle-import") (part "TACTILE_SWITCH6.2MM"))
    )
    (comp (ref "X1")
      (value "FTDI")
      (footprint "eagle-import:1X06")
      (libsource (lib "eagle-import") (part "PINHD-1X6"))
    )
    (comp (ref "X2")
      (value "ISCP")
      (footprint "eagle-import:2X03")
      (libsource (lib "eagle-import") (part "PINHD-2X3"))
    )
    (comp (ref "X3")
      (value "RJ11-4HORIZ")
      (footprint "eagle-import:RJ11-4_HORIZ")
      (libsource (lib "eagle-import") (part "RJ11-4HORIZ"))
    )
    (comp (ref "X4")
      (value "RJ11-4HORIZ")
      (footprint "eagle-import:RJ11-4_HORIZ")
      (libsource (lib "eagle-import") (part "RJ11-4HORIZ"))
    )
    (comp (ref "XTAL1")
      (value "16MHz")
      (footprint "eagle-import:XTAL_5.0X3.2_4")
      (libsource (lib "eagle-import") (part "CRYSTAL_GND5X3.2"))
    )
    (comp (ref "XTAL2")
      (value "40MHz")
      (footprint "eagle-import:XTAL_5.0X3.2_4")
      (libsource (lib "eagle-import") (part "CRYSTAL_GND5X3.2"))
    )
    (comp (ref "C26")
      (value "100n")
      (footprint "eagle-import:C0805")
      (libsource (lib "eagle-import") (part "CAPACITOR0805"))
    )
    (comp (ref "C27")
      (value "100n")
      (footprint "eagle-import:C0805")
      (libsource (lib "eagle-import") (part "CAPACITOR0805"))
    )
    (comp (ref "C28")
      (value "100n")
      (footprint "eagle-import:C0805")
      (libsource (lib "eagle-import") (part "CAPACITOR0805"))
    )
    (comp (ref "C29")
      (value "100n")
      (footprint "eagle-import:C0805")
      (libsource (lib "eagle-import") (part "CAPACITOR0805"))
    )
    (comp (ref "C30")
      (value "100n")
      (footprint "eagle-import:C0805")
      (libsource (lib "eagle-import") (part "CAPACITOR0805"))
    )
    (comp (ref "D33")
      (value "1N4148")
      (footprint "eagle-import:SOD123")
      (libsource (lib "eagle-import") (part "DIODESOD-123"))
    )
    (comp (ref "D34")
      (value "1N4148")
      (footprint "eagle-import:SOD123")
      (libsource (lib "eagle-import") (part "DIODESOD-123"))
    )
    (comp (ref "IC11")
      (value "MCP23008")
      (footprint "eagle-import:SO18W")
      (libsource (lib "eagle-import") (part "MCP23008SO18W"))
    )
    (comp (ref "IC12")
      (value "4051")
      (footprint "eagle-import:SO16")
      (libsource (lib "eagle-import") (part "4051SO16"))
    )
    (comp (ref "IC13")
      (value "4051")
      (footprint "eagle-import:SO16")
      (libsource (lib "eagle-import") (part "4051SO16"))
    )
    (comp (ref "IC14")
      (value "MCP23008")
      (footprint "eagle-import:SO18W")
      (libsource (lib "eagle-import") (part "MCP23008SO18W"))
    )
    (comp (ref "IC15")
      (value "MCP23008")
      (footprint "eagle-import:SO18W")
      (libsource (lib "eagle-import") (part "MCP23008SO18W"))
    )
    (comp (ref "R62")
      (value "10k")
      (footprint "eagle-import:R0805")
      (libsource (lib "eagle-import") (part "RESISTOR0805"))
    )
    (comp (ref "R63")
      (value "10k")
      (footprint "eagle-import:R0805")
      (libsource (lib "eagle-import") (part "RESISTOR0805"))
    )
    (comp (ref "R64")
      (value "10k")
      (footprint "eagle-import:R0805")
      (libsource (lib "eagle-import") (part "RESISTOR0805"))
    )
    (comp (ref "S10")
      (value "SWITCH_DIL08")
      (footprint "eagle-import:CTS-219-08")
      (libsource (lib "eagle-import") (part "SWITCH_DIL08"))
    )
  )
  (nets
    (net (code "1") (name "+12V") (class "Default")
      (node (ref "C24") (pin "1") (pinfunction "1_1") (pintype "passive"))
      (node (ref "C25") (pin "1") (pinfunction "1_1") (pintype "passive"))
      (node (ref "IC10") (pin "4") (pinfunction "EN_4") (pintype "bidirectional"))
      (node (ref "IC10") (pin "5") (pinfunction "VIN_5") (pintype "bidirectional"))
      (node (ref "X3") (pin "1") (pinfunction "1_1") (pintype "passive"))
      (node (ref "X4") (pin "1") (pinfunction "1_1") (pintype "passive"))
    )
    (net (code "2") (name "ADC_MUX_A") (class "Default")
      (node (ref "IC12") (pin "11") (pinfunction "A_11") (pintype "input"))
      (node (ref "IC13") (pin "11") (pinfunction "A_11") (pintype "input"))
      (node (ref "IC9") (pin "9") (pinfunction "PD5(T1)_9") (pintype "bidirectional"))
    )
    (net (code "3") (name "ADC_MUX_B") (class "Default")
      (node (ref "IC12") (pin "10") (pinfunction "B_10") (pintype "input"))
      (node (ref "IC13") (pin "10") (pinfunction "B_10") (pintype "input"))
      (node (ref "IC9") (pin "10") (pinfunction "PD6(AIN0)_10") (pintype "bidirectional"))
    )
    (net (code "4") (name "ADC_MUX_C") (class "Default")
      (node (ref "IC12") (pin "9") (pinfunction "C_9") (pintype "input"))
      (node (ref "IC13") (pin "9") (pinfunction "C_9") (pintype "input"))
      (node (ref "IC9") (pin "11") (pinfunction "PD7(AIN1)_11") (pintype "bidirectional"))
    )
    (net (code "5") (name "GND") (class "Default")
      (node (ref "C1") (pin "2") (pinfunction "2_2") (pintype "passive"))
      (node (ref "C10") (pin "2") (pinfunction "2_2") (pintype "passive"))
      (node (ref "C11") (pin "2") (pinfunction "2_2") (pintype "passive"))
      (node (ref "C12") (pin "2") (pinfunction "2_2") (pintype "passive"))
      (node (ref "C13") (pin "2") (pinfunction "2_2") (pintype "passive"))
      (node (ref "C14") (pin "2") (pinfunction "2_2") (pintype "passive"))
      (node (ref "C15") (pin "2") (pinfunction "2_2") (pintype "passive"))
      (node (ref "C16") (pin "2") (pinfunction "2_2") (pintype "passive"))
      (node (ref "C17") (pin "2") (pinfunction "2_2") (pintype "passive"))
      (node (ref "C18") (pin "2") (pinfunction "2_2") (pintype "passive"))
      (node (ref "C19") (pin "2") (pinfunction "2_2") (pintype "passive"))
      (node (ref "C2") (pin "2") (pinfunction "2_2") (pintype "passive"))
      (node (ref "C20") (pin "2") (pinfunction "2_2") (pintype "passive"))
      (node (ref "C22") (pin "1") (pinfunction "1_1") (pintype "passive"))
      (node (ref "C24") (pin "2") (pinfunction "2_2") (pintype "passive"))
      (node (ref "C25") (pin "2") (pinfunction "2_2") (pintype "passive"))
      (node (ref "C26") (pin "1") (pinfunction "1_1") (pintype "passive"))
      (node (ref "C27") (pin "2") (pinfunction "2_2") (pintype "passive"))
      (node (ref "C28") (pin "2") (pinfunction "2_2") (pintype "passive"))
      (node (ref "C29") (pin "1") (pinfunction "1_1") (pintype "passive"))
      (node (ref "C3") (pin "2") (pinfunction "2_2") (pintype "passive"))
      (node (ref "C30") (pin "1") (pinfunction "1_1") (pintype "passive"))
      (node (ref "C31") (pin "2") (pinfunction "2_2") (pintype "passive"))
      (node (ref "C32") (pin "1") (pinfunction "1_1") (pintype "passive"))
      (node (ref "C33") (pin "1") (pinfunction "1_1") (pintype "passive"))
      (node (ref "C34") (pin "2") (pinfunction "2_2") (pintype "passive"))
      (node (ref "C35") (pin "1") (pinfunction "1_1") (pintype "passive"))
      (node (ref "C4") (pin "2") (pinfunction "2_2") (pintype "passive"))
      (node (ref "C5") (pin "2") (pinfunction "2_2") (pintype "passive"))
      (node (ref "C6") (pin "2") (pinfunction "2_2") (pintype "passive"))
      (node (ref "C7") (pin "2") (pinfunction "2_2") (pintype "passive"))
      (node (ref "C8") (pin "2") (pinfunction "2_2") (pintype "passive"))
      (node (ref "C9") (pin "2") (pinfunction "2_2") (pintype "passive"))
      (node (ref "D35") (pin "C") (pinfunction "C_C") (pintype "passive"))
      (node (ref "D36") (pin "C") (pinfunction "C_C") (pintype "passive"))
      (node (ref "H1") (pin "B3,2") (pinfunction "MOUNT_B3,2") (pintype "passive"))
      (node (ref "H1") (pin "P$1") (pinfunction "MOUNT_P$1") (pintype "passive"))
      (node (ref "H1") (pin "P$2") (pinfunction "MOUNT_P$2") (pintype "passive"))
      (node (ref "H1") (pin "P$3") (pinfunction "MOUNT_P$3") (pintype "passive"))
      (node (ref "H1") (pin "P$4") (pinfunction "MOUNT_P$4") (pintype "passive"))
      (node (ref "H1") (pin "P$5") (pinfunction "MOUNT_P$5") (pintype "passive"))
      (node (ref "H1") (pin "P$6") (pinfunction "MOUNT_P$6") (pintype "passive"))
      (node (ref "H1") (pin "P$7") (pinfunction "MOUNT_P$7") (pintype "passive"))
      (node (ref "H1") (pin "P$8") (pinfunction "MOUNT_P$8") (pintype "passive"))
      (node (ref "H2") (pin "B3,2") (pinfunction "MOUNT_B3,2") (pintype "passive"))
      (node (ref "H2") (pin "P$1") (pinfunction "MOUNT_P$1") (pintype "passive"))
      (node (ref "H2") (pin "P$2") (pinfunction "MOUNT_P$2") (pintype "passive"))
      (node (ref "H2") (pin "P$3") (pinfunction "MOUNT_P$3") (pintype "passive"))
      (node (ref "H2") (pin "P$4") (pinfunction "MOUNT_P$4") (pintype "passive"))
      (node (ref "H2") (pin "P$5") (pinfunction "MOUNT_P$5") (pintype "passive"))
      (node (ref "H2") (pin "P$6") (pinfunction "MOUNT_P$6") (pintype "passive"))
      (node (ref "H2") (pin "P$7") (pinfunction "MOUNT_P$7") (pintype "passive"))
      (node (ref "H2") (pin "P$8") (pinfunction "MOUNT_P$8") (pintype "passive"))
      (node (ref "H3") (pin "B3,2") (pinfunction "MOUNT_B3,2") (pintype "passive"))
      (node (ref "H3") (pin "P$1") (pinfunction "MOUNT_P$1") (pintype "passive"))
      (node (ref "H3") (pin "P$2") (pinfunction "MOUNT_P$2") (pintype "passive"))
      (node (ref "H3") (pin "P$3") (pinfunction "MOUNT_P$3") (pintype "passive"))
      (node (ref "H3") (pin "P$4") (pinfunction "MOUNT_P$4") (pintype "passive"))
      (node (ref "H3") (pin "P$5") (pinfunction "MOUNT_P$5") (pintype "passive"))
      (node (ref "H3") (pin "P$6") (pinfunction "MOUNT_P$6") (pintype "passive"))
      (node (ref "H3") (pin "P$7") (pinfunction "MOUNT_P$7") (pintype "passive"))
      (node (ref "H3") (pin "P$8") (pinfunction "MOUNT_P$8") (pintype "passive"))
      (node (ref "H4") (pin "B3,2") (pinfunction "MOUNT_B3,2") (pintype "passive"))
      (node (ref "H4") (pin "P$1") (pinfunction "MOUNT_P$1") (pintype "passive"))
      (node (ref "H4") (pin "P$2") (pinfunction "MOUNT_P$2") (pintype "passive"))
      (node (ref "H4") (pin "P$3") (pinfunction "MOUNT_P$3") (pintype "passive"))
      (node (ref "H4") (pin "P$4") (pinfunction "MOUNT_P$4") (pintype "passive"))
      (node (ref "H4") (pin "P$5") (pinfunction "MOUNT_P$5") (pintype "passive"))
      (node (ref "H4") (pin "P$6") (pinfunction "MOUNT_P$6") (pintype "passive"))
      (node (ref "H4") (pin "P$7") (pinfunction "MOUNT_P$7") (pintype "passive"))
      (node (ref "H4") (pin "P$8") (pinfunction "MOUNT_P$8") (pintype "passive"))
      (node (ref "IC1") (pin "5") (pinfunction "GND_5") (pintype "bidirectional"))
      (node (ref "IC10") (pin "2") (pinfunction "GND_2") (pintype "bidirectional"))
      (node (ref "IC11") (pin "3") (pinfunction "A2_3") (pintype "bidirectional"))
      (node (ref "IC11") (pin "4") (pinfunction "A1_4") (pintype "bidirectional"))
      (node (ref "IC11") (pin "9") (pinfunction "GND_9") (pintype "bidirectional"))
      (node (ref "IC12") (pin "7") (pinfunction "VEE_7") (pintype "bidirectional"))
      (node (ref "IC12") (pin "8") (pinfunction "GND_8") (pintype "bidirectional"))
      (node (ref "IC13") (pin "7") (pinfunction "VEE_7") (pintype "bidirectional"))
      (node (ref "IC13") (pin "8") (pinfunction "GND_8") (pintype "bidirectional"))
      (node (ref "IC14") (pin "3") (pinfunction "A2_3") (pintype "bidirectional"))
      (node (ref "IC14") (pin "4") (pinfunction "A1_4") (pintype "bidirectional"))
      (node (ref "IC14") (pin "5") (pinfunction "A0_5") (pintype "bidirectional"))
      (node (ref "IC14") (pin "9") (pinfunction "GND_9") (pintype "bidirectional"))
      (node (ref "IC15") (pin "3") (pinfunction "A2_3") (pintype "bidirectional"))
      (node (ref "IC15") (pin "9") (pinfunction "GND_9") (pintype "bidirectional"))
      (node (ref "IC16") (pin "7") (pinfunction "GND_7") (pintype "bidirectional"))
      (node (ref "IC17") (pin "2") (pinfunction "GND_2") (pintype "bidirectional"))
      (node (ref "IC17") (pin "8") (pinfunction "STBY_8") (pintype "bidirectional"))
      (node (ref "IC2") (pin "5") (pinfunction "GND_5") (pintype "bidirectional"))
      (node (ref "IC3") (pin "5") (pinfunction "GND_5") (pintype "bidirectional"))
      (node (ref "IC4") (pin "5") (pinfunction "GND_5") (pintype "bidirectional"))
      (node (ref "IC5") (pin "5") (pinfunction "GND_5") (pintype "bidirectional"))
      (node (ref "IC6") (pin "5") (pinfunction "GND_5") (pintype "bidirectional"))
      (node (ref "IC7") (pin "5") (pinfunction "GND_5") (pintype "bidirectional"))
      (node (ref "IC8") (pin "5") (pinfunction "GND_5") (pintype "bidirectional"))
      (node (ref "IC9") (pin "21") (pinfunction "AGND_21") (pintype "bidirectional"))
      (node (ref "IC9") (pin "3") (pinfunction "GND_3") (pintype "bidirectional"))
      (node (ref "IC9") (pin "5") (pinfunction "GND_5") (pintype "bidirectional"))
      (node (ref "OK1") (pin "2") (pinfunction "C_2") (pintype "passive"))
      (node (ref "OK2") (pin "2") (pinfunction "C_2") (pintype "passive"))
      (node (ref "OK3") (pin "2") (pinfunction "C_2") (pintype "passive"))
      (node (ref "OK4") (pin "2") (pinfunction "C_2") (pintype "passive"))
      (node (ref "OK5") (pin "2") (pinfunction "C_2") (pintype "passive"))
      (node (ref "OK6") (pin "2") (pinfunction "C_2") (pintype "passive"))
      (node (ref "OK7") (pin "2") (pinfunction "C_2") (pintype "passive"))
      (node (ref "OK8") (pin "2") (pinfunction "C_2") (pintype "passive"))
      (node (ref "Q1") (pin "1") (pinfunction "S_1") (pintype "passive"))
      (node (ref "Q1") (pin "2") (pinfunction "S_2") (pintype "passive"))
      (node (ref "Q10") (pin "1") (pinfunction "S_1") (pintype "passive"))
      (node (ref "Q10") (pin "2") (pinfunction "S_2") (pintype "passive"))
      (node (ref "Q12") (pin "1") (pinfunction "S_1") (pintype "passive"))
      (node (ref "Q12") (pin "2") (pinfunction "S_2") (pintype "passive"))
      (node (ref "Q14") (pin "1") (pinfunction "S_1") (pintype "passive"))
      (node (ref "Q14") (pin "2") (pinfunction "S_2") (pintype "passive"))
      (node (ref "Q16") (pin "1") (pinfunction "S_1") (pintype "passive"))
      (node (ref "Q16") (pin "2") (pinfunction "S_2") (pintype "passive"))
      (node (ref "Q3") (pin "1") (pinfunction "S_1") (pintype "passive"))
      (node (ref "Q3") (pin "2") (pinfunction "S_2") (pintype "passive"))
      (node (ref "Q5") (pin "1") (pinfunction "S_1") (pintype "passive"))
      (node (ref "Q5") (pin "2") (pinfunction "S_2") (pintype "passive"))
      (node (ref "Q7") (pin "1") (pinfunction "S_1") (pintype "passive"))
      (node (ref "Q7") (pin "2") (pinfunction "S_2") (pintype "passive"))
      (node (ref "R1") (pin "1") (pinfunction "1_1") (pintype "passive"))
      (node (ref "R13") (pin "1") (pinfunction "1_1") (pintype "passive"))
      (node (ref "R14") (pin "1") (pinfunction "1_1") (pintype "passive"))
      (node (ref "R15") (pin "1") (pinfunction "1_1") (pintype "passive"))
      (node (ref "R20") (pin "1") (pinfunction "1_1") (pintype "passive"))
      (node (ref "R21") (pin "1") (pinfunction "1_1") (pintype "passive"))
      (node (ref "R22") (pin "1") (pinfunction "1_1") (pintype "passive"))
      (node (ref "R27") (pin "1") (pinfunction "1_1") (pintype "passive"))
      (node (ref "R28") (pin "1") (pinfunction "1_1") (pintype "passive"))
      (node (ref "R29") (pin "1") (pinfunction "1_1") (pintype "passive"))
      (node (ref "R30") (pin "1") (pinfunction "1_1") (pintype "passive"))
      (node (ref "R34") (pin "1") (pinfunction "1_1") (pintype "passive"))
      (node (ref "R36") (pin "1") (pinfunction "1_1") (pintype "passive"))
      (node (ref "R37") (pin "1") (pinfunction "1_1") (pintype "passive"))
      (node (ref "R41") (pin "1") (pinfunction "1_1") (pintype "passive"))
      (node (ref "R43") (pin "1") (pinfunction "1_1") (pintype "passive"))
      (node (ref "R44") (pin "1") (pinfunction "1_1") (pintype "passive"))
      (node (ref "R48") (pin "1") (pinfunction "1_1") (pintype "passive"))
      (node (ref "R50") (pin "1") (pinfunction "1_1") (pintype "passive"))
      (node (ref "R51") (pin "1") (pinfunction "1_1") (pintype "passive"))
      (node (ref "R55") (pin "1") (pinfunction "1_1") (pintype "passive"))
      (node (ref "R6") (pin "1") (pinfunction "1_1") (pintype "passive"))
      (node (ref "R61") (pin "1") (pinfunction "1_1") (pintype "passive"))
      (node (ref "R7") (pin "1") (pinfunction "1_1") (pintype "passive"))
      (node (ref "R8") (pin "1") (pinfunction "1_1") (pintype "passive"))
      (node (ref "S1") (pin "A1") (pinfunction "1_A1") (pintype "passive"))
      (node (ref "S1") (pin "A2") (pinfunction "1_A2") (pintype "passive"))
      (node (ref "S10") (pin "10") (pinfunction "10_10") (pintype "passive"))
      (node (ref "S10") (pin "11") (pinfunction "11_11") (pintype "passive"))
      (node (ref "S10") (pin "12") (pinfunction "12_12") (pintype "passive"))
      (node (ref "S10") (pin "13") (pinfunction "13_13") (pintype "passive"))
      (node (ref "S10") (pin "14") (pinfunction "14_14") (pintype "passive"))
      (node (ref "S10") (pin "15") (pinfunction "15_15") (pintype "passive"))
      (node (ref "S10") (pin "16") (pinfunction "16_16") (pintype "passive"))
      (node (ref "S10") (pin "9") (pinfunction "9_9") (pintype "passive"))
      (node (ref "S2") (pin "A1") (pinfunction "1_A1") (pintype "passive"))
      (node (ref "S2") (pin "A2") (pinfunction "1_A2") (pintype "passive"))
      (node (ref "S3") (pin "A1") (pinfunction "1_A1") (pintype "passive"))
      (node (ref "S3") (pin "A2") (pinfunction "1_A2") (pintype "passive"))
      (node (ref "S4") (pin "A1") (pinfunction "1_A1") (pintype "passive"))
      (node (ref "S4") (pin "A2") (pinfunction "1_A2") (pintype "passive"))
      (node (ref "S5") (pin "A1") (pinfunction "1_A1") (pintype "passive"))
      (node (ref "S5") (pin "A2") (pinfunction "1_A2") (pintype "passive"))
      (node (ref "S6") (pin "A1") (pinfunction "1_A1") (pintype "passive"))
      (node (ref "S6") (pin "A2") (pinfunction "1_A2") (pintype "passive"))
      (node (ref "S7") (pin "A1") (pinfunction "1_A1") (pintype "passive"))
      (node (ref "S7") (pin "A2") (pinfunction "1_A2") (pintype "passive"))
      (node (ref "S8") (pin "A1") (pinfunction "1_A1") (pintype "passive"))
      (node (ref "S8") (pin "A2") (pinfunction "1_A2") (pintype "passive"))
      (node (ref "S9") (pin "A1") (pinfunction "1_A1") (pintype "passive"))
      (node (ref "S9") (pin "A2") (pinfunction "1_A2") (pintype "passive"))
      (node (ref "X1") (pin "1") (pinfunction "1_1") (pintype "passive"))
      (node (ref "X1") (pin "2") (pinfunction "2_2") (pintype "passive"))
      (node (ref "X10") (pin "1") (pinfunction "PIN_1") (pintype "bidirectional"))
      (node (ref "X10") (pin "2") (pinfunction "PIN_2") (pintype "bidirectional"))
      (node (ref "X10") (pin "3") (pinfunction "PIN_3") (pintype "bidirectional"))
      (node (ref "X10") (pin "4") (pinfunction "PIN_4") (pintype "bidirectional"))
      (node (ref "X10") (pin "5") (pinfunction "PIN_5") (pintype "bidirectional"))
      (node (ref "X10") (pin "6") (pinfunction "PIN_6") (pintype "bidirectional"))
      (node (ref "X14") (pin "1") (pinfunction "PIN_1") (pintype "bidirectional"))
      (node (ref "X14") (pin "2") (pinfunction "PIN_2") (pintype "bidirectional"))
      (node (ref "X14") (pin "3") (pinfunction "PIN_3") (pintype "bidirectional"))
      (node (ref "X14") (pin "4") (pinfunction "PIN_4") (pintype "bidirectional"))
      (node (ref "X14") (pin "5") (pinfunction "PIN_5") (pintype "bidirectional"))
      (node (ref "X14") (pin "6") (pinfunction "PIN_6") (pintype "bidirectional"))
      (node (ref "X18") (pin "1") (pinfunction "PIN_1") (pintype "bidirectional"))
      (node (ref "X18") (pin "2") (pinfunction "PIN_2") (pintype "bidirectional"))
      (node (ref "X18") (pin "3") (pinfunction "PIN_3") (pintype "bidirectional"))
      (node (ref "X18") (pin "4") (pinfunction "PIN_4") (pintype "bidirectional"))
      (node (ref "X18") (pin "5") (pinfunction "PIN_5") (pintype "bidirectional"))
      (node (ref "X18") (pin "6") (pinfunction "PIN_6") (pintype "bidirectional"))
      (node (ref "X2") (pin "6") (pinfunction "6_6") (pintype "passive"))
      (node (ref "X22") (pin "1") (pinfunction "PIN_1") (pintype "bidirectional"))
      (node (ref "X22") (pin "2") (pinfunction "PIN_2") (pintype "bidirectional"))
      (node (ref "X22") (pin "3") (pinfunction "PIN_3") (pintype "bidirectional"))
      (node (ref "X22") (pin "4") (pinfunction "PIN_4") (pintype "bidirectional"))
      (node (ref "X22") (pin "5") (pinfunction "PIN_5") (pintype "bidirectional"))
      (node (ref "X22") (pin "6") (pinfunction "PIN_6") (pintype "bidirectional"))
      (node (ref "X26") (pin "1") (pinfunction "PIN_1") (pintype "bidirectional"))
      (node (ref "X26") (pin "2") (pinfunction "PIN_2") (pintype "bidirectional"))
      (node (ref "X26") (pin "3") (pinfunction "PIN_3") (pintype "bidirectional"))
      (node (ref "X26") (pin "4") (pinfunction "PIN_4") (pintype "bidirectional"))
      (node (ref "X26") (pin "5") (pinfunction "PIN_5") (pintype "bidirectional"))
      (node (ref "X26") (pin "6") (pinfunction "PIN_6") (pintype "bidirectional"))
      (node (ref "X3") (pin "4") (pinfunction "4_4") (pintype "passive"))
      (node (ref "X30") (pin "1") (pinfunction "PIN_1") (pintype "bidirectional"))
      (node (ref "X30") (pin "2") (pinfunction "PIN_2") (pintype "bidirectional"))
      (node (ref "X30") (pin "3") (pinfunction "PIN_3") (pintype "bidirectional"))
      (node (ref "X30") (pin "4") (pinfunction "PIN_4") (pintype "bidirectional"))
      (node (ref "X30") (pin "5") (pinfunction "PIN_5") (pintype "bidirectional"))
      (node (ref "X30") (pin "6") (pinfunction "PIN_6") (pintype "bidirectional"))
      (node (ref "X34") (pin "1") (pinfunction "PIN_1") (pintype "bidirectional"))
      (node (ref "X34") (pin "2") (pinfunction "PIN_2") (pintype "bidirectional"))
      (node (ref "X34") (pin "3") (pinfunction "PIN_3") (pintype "bidirectional"))
      (node (ref "X34") (pin "4") (pinfunction "PIN_4") (pintype "bidirectional"))
      (node (ref "X34") (pin "5") (pinfunction "PIN_5") (pintype "bidirectional"))
      (node (ref "X34") (pin "6") (pinfunction "PIN_6") (pintype "bidirectional"))
      (node (ref "X38") (pin "1") (pinfunction "PIN_1") (pintype "bidirectional"))
      (node (ref "X38") (pin "2") (pinfunction "PIN_2") (pintype "bidirectional"))
      (node (ref "X38") (pin "3") (pinfunction "PIN_3") (pintype "bidirectional"))
      (node (ref "X38") (pin "4") (pinfunction "PIN_4") (pintype "bidirectional"))
      (node (ref "X38") (pin "5") (pinfunction "PIN_5") (pintype "bidirectional"))
      (node (ref "X38") (pin "6") (pinfunction "PIN_6") (pintype "bidirectional"))
      (node (ref "X4") (pin "4") (pinfunction "4_4") (pintype "passive"))
      (node (ref "XTAL1") (pin "2") (pinfunction "2_2") (pintype "passive"))
      (node (ref "XTAL1") (pin "4") (pinfunction "2_4") (pintype "passive"))
      (node (ref "XTAL2") (pin "2") (pinfunction "2_2") (pintype "passive"))
      (node (ref "XTAL2") (pin "4") (pinfunction "2_4") (pintype "passive"))
    )
    (net (code "6") (name "I2C_SCL") (class "Default")
      (node (ref "IC11") (pin "1") (pinfunction "SCL_1") (pintype "bidirectional"))
      (node (ref "IC14") (pin "1") (pinfunction "SCL_1") (pintype "bidirectional"))
      (node (ref "IC15") (pin "1") (pinfunction "SCL_1") (pintype "bidirectional"))
      (node (ref "IC9") (pin "28") (pinfunction "PC5(ADC5/SCL)_28") (pintype "bidirectional"))
      (node (ref "R58") (pin "1") (pinfunction "1_1") (pintype "passive"))
    )
    (net (code "7") (name "I2C_SDA") (class "Default")
      (node (ref "IC11") (pin "2") (pinfunction "SDA_2") (pintype "bidirectional"))
      (node (ref "IC14") (pin "2") (pinfunction "SDA_2") (pintype "bidirectional"))
      (node (ref "IC15") (pin "2") (pinfunction "SDA_2") (pintype "bidirectional"))
      (node (ref "IC9") (pin "27") (pinfunction "PC4(ADC4/SDA)_27") (pintype "bidirectional"))
      (node (ref "R59") (pin "2") (pinfunction "2_2") (pintype "passive"))
    )
    (net (code "8") (name "INT_BTN") (class "Default")
      (node (ref "D33") (pin "C") (pinfunction "C_C") (pintype "passive"))
      (node (ref "D34") (pin "C") (pinfunction "C_C") (pintype "passive"))
      (node (ref "IC9") (pin "32") (pinfunction "PD2(INT0)_32") (pintype "bidirectional"))
    )
    (net (code "9") (name "INT_CAN") (class "Default")
      (node (ref "IC16") (pin "4") (pinfunction "INT_4") (pintype "bidirectional"))
      (node (ref "IC9") (pin "1") (pinfunction "PD3(INT1)_1") (pintype "bidirectional"))
    )
    (net (code "10") (name "IV_OUT_A") (class "Default")
      (node (ref "IC13") (pin "3") (pinfunction "X_3") (pintype "bidirectional"))
      (node (ref "IC9") (pin "23") (pinfunction "PC0(ADC0)_23") (pintype "bidirectional"))
    )
    (net (code "11") (name "IV_OUT_B") (class "Default")
      (node (ref "IC12") (pin "3") (pinfunction "X_3") (pintype "bidirectional"))
      (node (ref "IC9") (pin "24") (pinfunction "PC1(ADC1)_24") (pintype "bidirectional"))
    )
    (net (code "12") (name "I_OUT_1") (class "Default")
      (node (ref "IC1") (pin "7") (pinfunction "VI_OUT_7") (pintype "bidirectional"))
      (node (ref "IC12") (pin "13") (pinfunction "X0_13") (pintype "bidirectional"))
    )
    (net (code "13") (name "I_OUT_2") (class "Default")
      (node (ref "IC12") (pin "15") (pinfunction "X2_15") (pintype "bidirectional"))
      (node (ref "IC2") (pin "7") (pinfunction "VI_OUT_7") (pintype "bidirectional"))
    )
    (net (code "14") (name "I_OUT_3") (class "Default")
      (node (ref "IC12") (pin "2") (pinfunction "X6_2") (pintype "bidirectional"))
      (node (ref "IC3") (pin "7") (pinfunction "VI_OUT_7") (pintype "bidirectional"))
    )
    (net (code "15") (name "I_OUT_4") (class "Default")
      (node (ref "IC12") (pin "5") (pinfunction "X5_5") (pintype "bidirectional"))
      (node (ref "IC4") (pin "7") (pinfunction "VI_OUT_7") (pintype "bidirectional"))
    )
    (net (code "16") (name "I_OUT_5") (class "Default")
      (node (ref "IC13") (pin "1") (pinfunction "X4_1") (pintype "bidirectional"))
      (node (ref "IC5") (pin "7") (pinfunction "VI_OUT_7") (pintype "bidirectional"))
    )
    (net (code "17") (name "I_OUT_6") (class "Default")
      (node (ref "IC13") (pin "4") (pinfunction "X7_4") (pintype "bidirectional"))
      (node (ref "IC6") (pin "7") (pinfunction "VI_OUT_7") (pintype "bidirectional"))
    )
    (net (code "18") (name "I_OUT_7") (class "Default")
      (node (ref "IC13") (pin "12") (pinfunction "X3_12") (pintype "bidirectional"))
      (node (ref "IC7") (pin "7") (pinfunction "VI_OUT_7") (pintype "bidirectional"))
    )
    (net (code "19") (name "I_OUT_8") (class "Default")
      (node (ref "IC13") (pin "14") (pinfunction "X1_14") (pintype "bidirectional"))
      (node (ref "IC8") (pin "7") (pinfunction "VI_OUT_7") (pintype "bidirectional"))
    )
    (net (code "20") (name "LED") (class "Default")
      (node (ref "IC9") (pin "12") (pinfunction "PB0(ICP)_12") (pintype "bidirectional"))
      (node (ref "R66") (pin "2") (pinfunction "2_2") (pintype "passive"))
    )
    (net (code "21") (name "MOSFET_1") (class "Default")
      (node (ref "IC14") (pin "14") (pinfunction "GPIO4_14") (pintype "bidirectional"))
      (node (ref "R2") (pin "1") (pinfunction "1_1") (pintype "passive"))
    )
    (net (code "22") (name "MOSFET_2") (class "Default")
      (node (ref "IC14") (pin "15") (pinfunction "GPIO5_15") (pintype "bidirectional"))
      (node (ref "R9") (pin "1") (pinfunction "1_1") (pintype "passive"))
    )
    (net (code "23") (name "MOSFET_3") (class "Default")
      (node (ref "IC14") (pin "16") (pinfunction "GPIO6_16") (pintype "bidirectional"))
      (node (ref "R16") (pin "1") (pinfunction "1_1") (pintype "passive"))
    )
    (net (code "24") (name "MOSFET_4") (class "Default")
      (node (ref "IC14") (pin "17") (pinfunction "GPIO7_17") (pintype "bidirectional"))
      (node (ref "R23") (pin "1") (pinfunction "1_1") (pintype "passive"))
    )
    (net (code "25") (name "MOSFET_5") (class "Default")
      (node (ref "IC14") (pin "10") (pinfunction "GPIO0_10") (pintype "bidirectional"))
      (node (ref "R35") (pin "1") (pinfunction "1_1") (pintype "passive"))
    )
    (net (code "26") (name "MOSFET_6") (class "Default")
      (node (ref "IC14") (pin "11") (pinfunction "GPIO1_11") (pintype "bidirectional"))
      (node (ref "R42") (pin "1") (pinfunction "1_1") (pintype "passive"))
    )
    (net (code "27") (name "MOSFET_7") (class "Default")
      (node (ref "IC14") (pin "12") (pinfunction "GPIO2_12") (pintype "bidirectional"))
      (node (ref "R49") (pin "1") (pinfunction "1_1") (pintype "passive"))
    )
    (net (code "28") (name "MOSFET_8") (class "Default")
      (node (ref "IC14") (pin "13") (pinfunction "GPIO3_13") (pintype "bidirectional"))
      (node (ref "R56") (pin "1") (pinfunction "1_1") (pintype "passive"))
    )
    (net (code "29") (name "Net-(C21-Pad1)") (class "Default")
      (node (ref "C21") (pin "1") (pinfunction "1_1") (pintype "passive"))
      (node (ref "X1") (pin "6") (pinfunction "6_6") (pintype "passive"))
    )
    (net (code "30") (name "Net-(D1-PadA)") (class "Default")
      (node (ref "D1") (pin "A") (pinfunction "A_A") (pintype "passive"))
      (node (ref "Q1") (pin "5") (pinfunction "D_5") (pintype "passive"))
      (node (ref "Q1") (pin "6") (pinfunction "D_6") (pintype "passive"))
      (node (ref "Q1") (pin "7") (pinfunction "D_7") (pintype "passive"))
      (node (ref "Q1") (pin "8") (pinfunction "D_8") (pintype "passive"))
      (node (ref "Q1") (pin "9") (pinfunction "D_9") (pintype "passive"))
      (node (ref "R3") (pin "1") (pinfunction "1_1") (pintype "passive"))
      (node (ref "X12") (pin "1") (pinfunction "PIN_1") (pintype "bidirectional"))
      (node (ref "X12") (pin "2") (pinfunction "PIN_2") (pintype "bidirectional"))
      (node (ref "X12") (pin "3") (pinfunction "PIN_3") (pintype "bidirectional"))
      (node (ref "X12") (pin "4") (pinfunction "PIN_4") (pintype "bidirectional"))
      (node (ref "X12") (pin "5") (pinfunction "PIN_5") (pintype "bidirectional"))
      (node (ref "X12") (pin "6") (pinfunction "PIN_6") (pintype "bidirectional"))
    )
    (net (code "31") (name "Net-(D1-PadC)") (class "Default")
      (node (ref "D1") (pin "C") (pinfunction "C_C") (pintype "passive"))
      (node (ref "D2") (pin "A") (pinfunction "A_A") (pintype "passive"))
      (node (ref "IC1") (pin "3") (pinfunction "I-_3") (pintype "bidirectional"))
      (node (ref "IC1") (pin "4") (pinfunction "I-_4") (pintype "bidirectional"))
      (node (ref "R4") (pin "2") (pinfunction "2_2") (pintype "passive"))
      (node (ref "X11") (pin "1") (pinfunction "PIN_1") (pintype "bidirectional"))
      (node (ref "X11") (pin "2") (pinfunction "PIN_2") (pintype "bidirectional"))
      (node (ref "X11") (pin "3") (pinfunction "PIN_3") (pintype "bidirectional"))
      (node (ref "X11") (pin "4") (pinfunction "PIN_4") (pintype "bidirectional"))
      (node (ref "X11") (pin "5") (pinfunction "PIN_5") (pintype "bidirectional"))
      (node (ref "X11") (pin "6") (pinfunction "PIN_6") (pintype "bidirectional"))
    )
    (net (code "32") (name "Net-(D2-PadC)") (class "Default")
      (node (ref "D2") (pin "C") (pinfunction "C_C") (pintype "passive"))
      (node (ref "R3") (pin "2") (pinfunction "2_2") (pintype "passive"))
    )
    (net (code "33") (name "Net-(D3-PadA)") (class "Default")
      (node (ref "D3") (pin "A") (pinfunction "A_A") (pintype "passive"))
      (node (ref "F1") (pin "2") (pinfunction "2_2") (pintype "passive"))
      (node (ref "F1") (pin "4") (pinfunction "2_4") (pintype "passive"))
      (node (ref "IC1") (pin "1") (pinfunction "I+_1") (pintype "bidirectional"))
      (node (ref "IC1") (pin "2") (pinfunction "I+_2") (pintype "bidirectional"))
    )
    (net (code "34") (name "Net-(D4-PadA)") (class "Default")
      (node (ref "D4") (pin "A") (pinfunction "A_A") (pintype "passive"))
      (node (ref "F1") (pin "1") (pinfunction "1_1") (pintype "passive"))
      (node (ref "F1") (pin "3") (pinfunction "1_3") (pintype "passive"))
      (node (ref "X9") (pin "1") (pinfunction "PIN_1") (pintype "bidirectional"))
      (node (ref "X9") (pin "2") (pinfunction "PIN_2") (pintype "bidirectional"))
      (node (ref "X9") (pin "3") (pinfunction "PIN_3") (pintype "bidirectional"))
      (node (ref "X9") (pin "4") (pinfunction "PIN_4") (pintype "bidirectional"))
      (node (ref "X9") (pin "5") (pinfunction "PIN_5") (pintype "bidirectional"))
      (node (ref "X9") (pin "6") (pinfunction "PIN_6") (pintype "bidirectional"))
    )
    (net (code "35") (name "Net-(D5-PadA)") (class "Default")
      (node (ref "D5") (pin "A") (pinfunction "A_A") (pintype "passive"))
      (node (ref "Q3") (pin "5") (pinfunction "D_5") (pintype "passive"))
      (node (ref "Q3") (pin "6") (pinfunction "D_6") (pintype "passive"))
      (node (ref "Q3") (pin "7") (pinfunction "D_7") (pintype "passive"))
      (node (ref "Q3") (pin "8") (pinfunction "D_8") (pintype "passive"))
      (node (ref "Q3") (pin "9") (pinfunction "D_9") (pintype "passive"))
      (node (ref "R10") (pin "1") (pinfunction "1_1") (pintype "passive"))
      (node (ref "X20") (pin "1") (pinfunction "PIN_1") (pintype "bidirectional"))
      (node (ref "X20") (pin "2") (pinfunction "PIN_2") (pintype "bidirectional"))
      (node (ref "X20") (pin "3") (pinfunction "PIN_3") (pintype "bidirectional"))
      (node (ref "X20") (pin "4") (pinfunction "PIN_4") (pintype "bidirectional"))
      (node (ref "X20") (pin "5") (pinfunction "PIN_5") (pintype "bidirectional"))
      (node (ref "X20") (pin "6") (pinfunction "PIN_6") (pintype "bidirectional"))
    )
    (net (code "36") (name "Net-(D5-PadC)") (class "Default")
      (node (ref "D5") (pin "C") (pinfunction "C_C") (pintype "passive"))
      (node (ref "D6") (pin "A") (pinfunction "A_A") (pintype "passive"))
      (node (ref "IC2") (pin "3") (pinfunction "I-_3") (pintype "bidirectional"))
      (node (ref "IC2") (pin "4") (pinfunction "I-_4") (pintype "bidirectional"))
      (node (ref "R11") (pin "2") (pinfunction "2_2") (pintype "passive"))
      (node (ref "X19") (pin "1") (pinfunction "PIN_1") (pintype "bidirectional"))
      (node (ref "X19") (pin "2") (pinfunction "PIN_2") (pintype "bidirectional"))
      (node (ref "X19") (pin "3") (pinfunction "PIN_3") (pintype "bidirectional"))
      (node (ref "X19") (pin "4") (pinfunction "PIN_4") (pintype "bidirectional"))
      (node (ref "X19") (pin "5") (pinfunction "PIN_5") (pintype "bidirectional"))
      (node (ref "X19") (pin "6") (pinfunction "PIN_6") (pintype "bidirectional"))
    )
    (net (code "37") (name "Net-(D6-PadC)") (class "Default")
      (node (ref "D6") (pin "C") (pinfunction "C_C") (pintype "passive"))
      (node (ref "R10") (pin "2") (pinfunction "2_2") (pintype "passive"))
    )
    (net (code "38") (name "Net-(D7-PadA)") (class "Default")
      (node (ref "D7") (pin "A") (pinfunction "A_A") (pintype "passive"))
      (node (ref "F2") (pin "2") (pinfunction "2_2") (pintype "passive"))
      (node (ref "F2") (pin "4") (pinfunction "2_4") (pintype "passive"))
      (node (ref "IC2") (pin "1") (pinfunction "I+_1") (pintype "bidirectional"))
      (node (ref "IC2") (pin "2") (pinfunction "I+_2") (pintype "bidirectional"))
    )
    (net (code "39") (name "Net-(D8-PadA)") (class "Default")
      (node (ref "D8") (pin "A") (pinfunction "A_A") (pintype "passive"))
      (node (ref "F2") (pin "1") (pinfunction "1_1") (pintype "passive"))
      (node (ref "F2") (pin "3") (pinfunction "1_3") (pintype "passive"))
      (node (ref "X17") (pin "1") (pinfunction "PIN_1") (pintype "bidirectional"))
      (node (ref "X17") (pin "2") (pinfunction "PIN_2") (pintype "bidirectional"))
      (node (ref "X17") (pin "3") (pinfunction "PIN_3") (pintype "bidirectional"))
      (node (ref "X17") (pin "4") (pinfunction "PIN_4") (pintype "bidirectional"))
      (node (ref "X17") (pin "5") (pinfunction "PIN_5") (pintype "bidirectional"))
      (node (ref "X17") (pin "6") (pinfunction "PIN_6") (pintype "bidirectional"))
    )
    (net (code "40") (name "Net-(D9-PadA)") (class "Default")
      (node (ref "D9") (pin "A") (pinfunction "A_A") (pintype "passive"))
      (node (ref "Q5") (pin "5") (pinfunction "D_5") (pintype "passive"))
      (node (ref "Q5") (pin "6") (pinfunction "D_6") (pintype "passive"))
      (node (ref "Q5") (pin "7") (pinfunction "D_7") (pintype "passive"))
      (node (ref "Q5") (pin "8") (pinfunction "D_8") (pintype "passive"))
      (node (ref "Q5") (pin "9") (pinfunction "D_9") (pintype "passive"))
      (node (ref "R17") (pin "1") (pinfunction "1_1") (pintype "passive"))
      (node (ref "X28") (pin "1") (pinfunction "PIN_1") (pintype "bidirectional"))
      (node (ref "X28") (pin "2") (pinfunction "PIN_2") (pintype "bidirectional"))
      (node (ref "X28") (pin "3") (pinfunction "PIN_3") (pintype "bidirectional"))
      (node (ref "X28") (pin "4") (pinfunction "PIN_4") (pintype "bidirectional"))
      (node (ref "X28") (pin "5") (pinfunction "PIN_5") (pintype "bidirectional"))
      (node (ref "X28") (pin "6") (pinfunction "PIN_6") (pintype "bidirectional"))
    )
    (net (code "41") (name "Net-(D10-PadA)") (class "Default")
      (node (ref "D10") (pin "A") (pinfunction "A_A") (pintype "passive"))
      (node (ref "D9") (pin "C") (pinfunction "C_C") (pintype "passive"))
      (node (ref "IC3") (pin "3") (pinfunction "I-_3") (pintype "bidirectional"))
      (node (ref "IC3") (pin "4") (pinfunction "I-_4") (pintype "bidirectional"))
      (node (ref "R18") (pin "2") (pinfunction "2_2") (pintype "passive"))
      (node (ref "X27") (pin "1") (pinfunction "PIN_1") (pintype "bidirectional"))
      (node (ref "X27") (pin "2") (pinfunction "PIN_2") (pintype "bidirectional"))
      (node (ref "X27") (pin "3") (pinfunction "PIN_3") (pintype "bidirectional"))
      (node (ref "X27") (pin "4") (pinfunction "PIN_4") (pintype "bidirectional"))
      (node (ref "X27") (pin "5") (pinfunction "PIN_5") (pintype "bidirectional"))
      (node (ref "X27") (pin "6") (pinfunction "PIN_6") (pintype "bidirectional"))
    )
    (net (code "42") (name "Net-(D10-PadC)") (class "Default")
      (node (ref "D10") (pin "C") (pinfunction "C_C") (pintype "passive"))
      (node (ref "R17") (pin "2") (pinfunction "2_2") (pintype "passive"))
    )
    (net (code "43") (name "Net-(D11-PadA)") (class "Default")
      (node (ref "D11") (pin "A") (pinfunction "A_A") (pintype "passive"))
      (node (ref "F3") (pin "2") (pinfunction "2_2") (pintype "passive"))
      (node (ref "F3") (pin "4") (pinfunction "2_4") (pintype "passive"))
      (node (ref "IC3") (pin "1") (pinfunction "I+_1") (pintype "bidirectional"))
      (node (ref "IC3") (pin "2") (pinfunction "I+_2") (pintype "bidirectional"))
    )
    (net (code "44") (name "Net-(D12-PadA)") (class "Default")
      (node (ref "D12") (pin "A") (pinfunction "A_A") (pintype "passive"))
      (node (ref "F3") (pin "1") (pinfunction "1_1") (pintype "passive"))
      (node (ref "F3") (pin "3") (pinfunction "1_3") (pintype "passive"))
      (node (ref "X25") (pin "1") (pinfunction "PIN_1") (pintype "bidirectional"))
      (node (ref "X25") (pin "2") (pinfunction "PIN_2") (pintype "bidirectional"))
      (node (ref "X25") (pin "3") (pinfunction "PIN_3") (pintype "bidirectional"))
      (node (ref "X25") (pin "4") (pinfunction "PIN_4") (pintype "bidirectional"))
      (node (ref "X25") (pin "5") (pinfunction "PIN_5") (pintype "bidirectional"))
      (node (ref "X25") (pin "6") (pinfunction "PIN_6") (pintype "bidirectional"))
    )
    (net (code "45") (name "Net-(D13-PadA)") (class "Default")
      (node (ref "D13") (pin "A") (pinfunction "A_A") (pintype "passive"))
      (node (ref "Q7") (pin "5") (pinfunction "D_5") (pintype "passive"))
      (node (ref "Q7") (pin "6") (pinfunction "D_6") (pintype "passive"))
      (node (ref "Q7") (pin "7") (pinfunction "D_7") (pintype "passive"))
      (node (ref "Q7") (pin "8") (pinfunction "D_8") (pintype "passive"))
      (node (ref "Q7") (pin "9") (pinfunction "D_9") (pintype "passive"))
      (node (ref "R24") (pin "1") (pinfunction "1_1") (pintype "passive"))
      (node (ref "X36") (pin "1") (pinfunction "PIN_1") (pintype "bidirectional"))
      (node (ref "X36") (pin "2") (pinfunction "PIN_2") (pintype "bidirectional"))
      (node (ref "X36") (pin "3") (pinfunction "PIN_3") (pintype "bidirectional"))
      (node (ref "X36") (pin "4") (pinfunction "PIN_4") (pintype "bidirectional"))
      (node (ref "X36") (pin "5") (pinfunction "PIN_5") (pintype "bidirectional"))
      (node (ref "X36") (pin "6") (pinfunction "PIN_6") (pintype "bidirectional"))
    )
    (net (code "46") (name "Net-(D13-PadC)") (class "Default")
      (node (ref "D13") (pin "C") (pinfunction "C_C") (pintype "passive"))
      (node (ref "D14") (pin "A") (pinfunction "A_A") (pintype "passive"))
      (node (ref "IC4") (pin "3") (pinfunction "I-_3") (pintype "bidirectional"))
      (node (ref "IC4") (pin "4") (pinfunction "I-_4") (pintype "bidirectional"))
      (node (ref "R25") (pin "2") (pinfunction "2_2") (pintype "passive"))
      (node (ref "X35") (pin "1") (pinfunction "PIN_1") (pintype "bidirectional"))
      (node (ref "X35") (pin "2") (pinfunction "PIN_2") (pintype "bidirectional"))
      (node (ref "X35") (pin "3") (pinfunction "PIN_3") (pintype "bidirectional"))
      (node (ref "X35") (pin "4") (pinfunction "PIN_4") (pintype "bidirectional"))
      (node (ref "X35") (pin "5") (pinfunction "PIN_5") (pintype "bidirectional"))
      (node (ref "X35") (pin "6") (pinfunction "PIN_6") (pintype "bidirectional"))
    )
    (net (code "47") (name "Net-(D14-PadC)") (class "Default")
      (node (ref "D14") (pin "C") (pinfunction "C_C") (pintype "passive"))
      (node (ref "R24") (pin "2") (pinfunction "2_2") (pintype "passive"))
    )
    (net (code "48") (name "Net-(D15-PadA)") (class "Default")
      (node (ref "D15") (pin "A") (pinfunction "A_A") (pintype "passive"))
      (node (ref "F4") (pin "2") (pinfunction "2_2") (pintype "passive"))
      (node (ref "F4") (pin "4") (pinfunction "2_4") (pintype "passive"))
      (node (ref "IC4") (pin "1") (pinfunction "I+_1") (pintype "bidirectional"))
      (node (ref "IC4") (pin "2") (pinfunction "I+_2") (pintype "bidirectional"))
    )
    (net (code "49") (name "Net-(D16-PadA)") (class "Default")
      (node (ref "D16") (pin "A") (pinfunction "A_A") (pintype "passive"))
      (node (ref "F4") (pin "1") (pinfunction "1_1") (pintype "passive"))
      (node (ref "F4") (pin "3") (pinfunction "1_3") (pintype "passive"))
      (node (ref "X33") (pin "1") (pinfunction "PIN_1") (pintype "bidirectional"))
      (node (ref "X33") (pin "2") (pinfunction "PIN_2") (pintype "bidirectional"))
      (node (ref "X33") (pin "3") (pinfunction "PIN_3") (pintype "bidirectional"))
      (node (ref "X33") (pin "4") (pinfunction "PIN_4") (pintype "bidirectional"))
      (node (ref "X33") (pin "5") (pinfunction "PIN_5") (pintype "bidirectional"))
      (node (ref "X33") (pin "6") (pinfunction "PIN_6") (pintype "bidirectional"))
    )
    (net (code "50") (name "Net-(D17-PadA)") (class "Default")
      (node (ref "D17") (pin "A") (pinfunction "A_A") (pintype "passive"))
      (node (ref "F5") (pin "1") (pinfunction "1_1") (pintype "passive"))
      (node (ref "F5") (pin "3") (pinfunction "1_3") (pintype "passive"))
      (node (ref "X37") (pin "1") (pinfunction "PIN_1") (pintype "bidirectional"))
      (node (ref "X37") (pin "2") (pinfunction "PIN_2") (pintype "bidirectional"))
      (node (ref "X37") (pin "3") (pinfunction "PIN_3") (pintype "bidirectional"))
      (node (ref "X37") (pin "4") (pinfunction "PIN_4") (pintype "bidirectional"))
      (node (ref "X37") (pin "5") (pinfunction "PIN_5") (pintype "bidirectional"))
      (node (ref "X37") (pin "6") (pinfunction "PIN_6") (pintype "bidirectional"))
    )
    (net (code "51") (name "Net-(D18-PadA)") (class "Default")
      (node (ref "D18") (pin "A") (pinfunction "A_A") (pintype "passive"))
      (node (ref "F5") (pin "2") (pinfunction "2_2") (pintype "passive"))
      (node (ref "F5") (pin "4") (pinfunction "2_4") (pintype "passive"))
      (node (ref "IC5") (pin "3") (pinfunction "I-_3") (pintype "bidirectional"))
      (node (ref "IC5") (pin "4") (pinfunction "I-_4") (pintype "bidirectional"))
    )
    (net (code "52") (name "Net-(D19-PadA)") (class "Default")
      (node (ref "D19") (pin "A") (pinfunction "A_A") (pintype "passive"))
      (node (ref "D20") (pin "C") (pinfunction "C_C") (pintype "passive"))
      (node (ref "IC5") (pin "1") (pinfunction "I+_1") (pintype "bidirectional"))
      (node (ref "IC5") (pin "2") (pinfunction "I+_2") (pintype "bidirectional"))
      (node (ref "R32") (pin "2") (pinfunction "2_2") (pintype "passive"))
      (node (ref "X39") (pin "1") (pinfunction "PIN_1") (pintype "bidirectional"))
      (node (ref "X39") (pin "2") (pinfunction "PIN_2") (pintype "bidirectional"))
      (node (ref "X39") (pin "3") (pinfunction "PIN_3") (pintype "bidirectional"))
      (node (ref "X39") (pin "4") (pinfunction "PIN_4") (pintype "bidirectional"))
      (node (ref "X39") (pin "5") (pinfunction "PIN_5") (pintype "bidirectional"))
      (node (ref "X39") (pin "6") (pinfunction "PIN_6") (pintype "bidirectional"))
    )
    (net (code "53") (name "Net-(D19-PadC)") (class "Default")
      (node (ref "D19") (pin "C") (pinfunction "C_C") (pintype "passive"))
      (node (ref "R33") (pin "2") (pinfunction "2_2") (pintype "passive"))
    )
    (net (code "54") (name "Net-(D20-PadA)") (class "Default")
      (node (ref "D20") (pin "A") (pinfunction "A_A") (pintype "passive"))
      (node (ref "Q10") (pin "5") (pinfunction "D_5") (pintype "passive"))
      (node (ref "Q10") (pin "6") (pinfunction "D_6") (pintype "passive"))
      (node (ref "Q10") (pin "7") (pinfunction "D_7") (pintype "passive"))
      (node (ref "Q10") (pin "8") (pinfunction "D_8") (pintype "passive"))
      (node (ref "Q10") (pin "9") (pinfunction "D_9") (pintype "passive"))
      (node (ref "R33") (pin "1") (pinfunction "1_1") (pintype "passive"))
      (node (ref "X40") (pin "1") (pinfunction "PIN_1") (pintype "bidirectional"))
      (node (ref "X40") (pin "2") (pinfunction "PIN_2") (pintype "bidirectional"))
      (node (ref "X40") (pin "3") (pinfunction "PIN_3") (pintype "bidirectional"))
      (node (ref "X40") (pin "4") (pinfunction "PIN_4") (pintype "bidirectional"))
      (node (ref "X40") (pin "5") (pinfunction "PIN_5") (pintype "bidirectional"))
      (node (ref "X40") (pin "6") (pinfunction "PIN_6") (pintype "bidirectional"))
    )
    (net (code "55") (name "Net-(D21-PadA)") (class "Default")
      (node (ref "D21") (pin "A") (pinfunction "A_A") (pintype "passive"))
      (node (ref "F6") (pin "1") (pinfunction "1_1") (pintype "passive"))
      (node (ref "F6") (pin "3") (pinfunction "1_3") (pintype "passive"))
      (node (ref "X29") (pin "1") (pinfunction "PIN_1") (pintype "bidirectional"))
      (node (ref "X29") (pin "2") (pinfunction "PIN_2") (pintype "bidirectional"))
      (node (ref "X29") (pin "3") (pinfunction "PIN_3") (pintype "bidirectional"))
      (node (ref "X29") (pin "4") (pinfunction "PIN_4") (pintype "bidirectional"))
      (node (ref "X29") (pin "5") (pinfunction "PIN_5") (pintype "bidirectional"))
      (node (ref "X29") (pin "6") (pinfunction "PIN_6") (pintype "bidirectional"))
    )
    (net (code "56") (name "Net-(D22-PadA)") (class "Default")
      (node (ref "D22") (pin "A") (pinfunction "A_A") (pintype "passive"))
      (node (ref "F6") (pin "2") (pinfunction "2_2") (pintype "passive"))
      (node (ref "F6") (pin "4") (pinfunction "2_4") (pintype "passive"))
      (node (ref "IC6") (pin "3") (pinfunction "I-_3") (pintype "bidirectional"))
      (node (ref "IC6") (pin "4") (pinfunction "I-_4") (pintype "bidirectional"))
    )
    (net (code "57") (name "Net-(D23-PadA)") (class "Default")
      (node (ref "D23") (pin "A") (pinfunction "A_A") (pintype "passive"))
      (node (ref "D24") (pin "C") (pinfunction "C_C") (pintype "passive"))
      (node (ref "IC6") (pin "1") (pinfunction "I+_1") (pintype "bidirectional"))
      (node (ref "IC6") (pin "2") (pinfunction "I+_2") (pintype "bidirectional"))
      (node (ref "R39") (pin "2") (pinfunction "2_2") (pintype "passive"))
      (node (ref "X31") (pin "1") (pinfunction "PIN_1") (pintype "bidirectional"))
      (node (ref "X31") (pin "2") (pinfunction "PIN_2") (pintype "bidirectional"))
      (node (ref "X31") (pin "3") (pinfunction "PIN_3") (pintype "bidirectional"))
      (node (ref "X31") (pin "4") (pinfunction "PIN_4") (pintype "bidirectional"))
      (node (ref "X31") (pin "5") (pinfunction "PIN_5") (pintype "bidirectional"))
      (node (ref "X31") (pin "6") (pinfunction "PIN_6") (pintype "bidirectional"))
    )
    (net (code "58") (name "Net-(D23-PadC)") (class "Default")
      (node (ref "D23") (pin "C") (pinfunction "C_C") (pintype "passive"))
      (node (ref "R40") (pin "2") (pinfunction "2_2") (pintype "passive"))
    )
    (net (code "59") (name "Net-(D24-PadA)") (class "Default")
      (node (ref "D24") (pin "A") (pinfunction "A_A") (pintype "passive"))
      (node (ref "Q12") (pin "5") (pinfunction "D_5") (pintype "passive"))
      (node (ref "Q12") (pin "6") (pinfunction "D_6") (pintype "passive"))
      (node (ref "Q12") (pin "7") (pinfunction "D_7") (pintype "passive"))
      (node (ref "Q12") (pin "8") (pinfunction "D_8") (pintype "passive"))
      (node (ref "Q12") (pin "9") (pinfunction "D_9") (pintype "passive"))
      (node (ref "R40") (pin "1") (pinfunction "1_1") (pintype "passive"))
      (node (ref "X32") (pin "1") (pinfunction "PIN_1") (pintype "bidirectional"))
      (node (ref "X32") (pin "2") (pinfunction "PIN_2") (pintype "bidirectional"))
      (node (ref "X32") (pin "3") (pinfunction "PIN_3") (pintype "bidirectional"))
      (node (ref "X32") (pin "4") (pinfunction "PIN_4") (pintype "bidirectional"))
      (node (ref "X32") (pin "5") (pinfunction "PIN_5") (pintype "bidirectional"))
      (node (ref "X32") (pin "6") (pinfunction "PIN_6") (pintype "bidirectional"))
    )
    (net (code "60") (name "Net-(D25-PadA)") (class "Default")
      (node (ref "D25") (pin "A") (pinfunction "A_A") (pintype "passive"))
      (node (ref "F7") (pin "1") (pinfunction "1_1") (pintype "passive"))
      (node (ref "F7") (pin "3") (pinfunction "1_3") (pintype "passive"))
      (node (ref "X21") (pin "1") (pinfunction "PIN_1") (pintype "bidirectional"))
      (node (ref "X21") (pin "2") (pinfunction "PIN_2") (pintype "bidirectional"))
      (node (ref "X21") (pin "3") (pinfunction "PIN_3") (pintype "bidirectional"))
      (node (ref "X21") (pin "4") (pinfunction "PIN_4") (pintype "bidirectional"))
      (node (ref "X21") (pin "5") (pinfunction "PIN_5") (pintype "bidirectional"))
      (node (ref "X21") (pin "6") (pinfunction "PIN_6") (pintype "bidirectional"))
    )
    (net (code "61") (name "Net-(D26-PadA)") (class "Default")
      (node (ref "D26") (pin "A") (pinfunction "A_A") (pintype "passive"))
      (node (ref "F7") (pin "2") (pinfunction "2_2") (pintype "passive"))
      (node (ref "F7") (pin "4") (pinfunction "2_4") (pintype "passive"))
      (node (ref "IC7") (pin "3") (pinfunction "I-_3") (pintype "bidirectional"))
      (node (ref "IC7") (pin "4") (pinfunction "I-_4") (pintype "bidirectional"))
    )
    (net (code "62") (name "Net-(D27-PadA)") (class "Default")
      (node (ref "D27") (pin "A") (pinfunction "A_A") (pintype "passive"))
      (node (ref "D28") (pin "C") (pinfunction "C_C") (pintype "passive"))
      (node (ref "IC7") (pin "1") (pinfunction "I+_1") (pintype "bidirectional"))
      (node (ref "IC7") (pin "2") (pinfunction "I+_2") (pintype "bidirectional"))
      (node (ref "R46") (pin "2") (pinfunction "2_2") (pintype "passive"))
      (node (ref "X23") (pin "1") (pinfunction "PIN_1") (pintype "bidirectional"))
      (node (ref "X23") (pin "2") (pinfunction "PIN_2") (pintype "bidirectional"))
      (node (ref "X23") (pin "3") (pinfunction "PIN_3") (pintype "bidirectional"))
      (node (ref "X23") (pin "4") (pinfunction "PIN_4") (pintype "bidirectional"))
      (node (ref "X23") (pin "5") (pinfunction "PIN_5") (pintype "bidirectional"))
      (node (ref "X23") (pin "6") (pinfunction "PIN_6") (pintype "bidirectional"))
    )
    (net (code "63") (name "Net-(D27-PadC)") (class "Default")
      (node (ref "D27") (pin "C") (pinfunction "C_C") (pintype "passive"))
      (node (ref "R47") (pin "2") (pinfunction "2_2") (pintype "passive"))
    )
    (net (code "64") (name "Net-(D28-PadA)") (class "Default")
      (node (ref "D28") (pin "A") (pinfunction "A_A") (pintype "passive"))
      (node (ref "Q14") (pin "5") (pinfunction "D_5") (pintype "passive"))
      (node (ref "Q14") (pin "6") (pinfunction "D_6") (pintype "passive"))
      (node (ref "Q14") (pin "7") (pinfunction "D_7") (pintype "passive"))
      (node (ref "Q14") (pin "8") (pinfunction "D_8") (pintype "passive"))
      (node (ref "Q14") (pin "9") (pinfunction "D_9") (pintype "passive"))
      (node (ref "R47") (pin "1") (pinfunction "1_1") (pintype "passive"))
      (node (ref "X24") (pin "1") (pinfunction "PIN_1") (pintype "bidirectional"))
      (node (ref "X24") (pin "2") (pinfunction "PIN_2") (pintype "bidirectional"))
      (node (ref "X24") (pin "3") (pinfunction "PIN_3") (pintype "bidirectional"))
      (node (ref "X24") (pin "4") (pinfunction "PIN_4") (pintype "bidirectional"))
      (node (ref "X24") (pin "5") (pinfunction "PIN_5") (pintype "bidirectional"))
      (node (ref "X24") (pin "6") (pinfunction "PIN_6") (pintype "bidirectional"))
    )
    (net (code "65") (name "Net-(D29-PadA)") (class "Default")
      (node (ref "D29") (pin "A") (pinfunction "A_A") (pintype "passive"))
      (node (ref "F8") (pin "1") (pinfunction "1_1") (pintype "passive"))
      (node (ref "F8") (pin "3") (pinfunction "1_3") (pintype "passive"))
      (node (ref "X13") (pin "1") (pinfunction "PIN_1") (pintype "bidirectional"))
      (node (ref "X13") (pin "2") (pinfunction "PIN_2") (pintype "bidirectional"))
      (node (ref "X13") (pin "3") (pinfunction "PIN_3") (pintype "bidirectional"))
      (node (ref "X13") (pin "4") (pinfunction "PIN_4") (pintype "bidirectional"))
      (node (ref "X13") (pin "5") (pinfunction "PIN_5") (pintype "bidirectional"))
      (node (ref "X13") (pin "6") (pinfunction "PIN_6") (pintype "bidirectional"))
    )
    (net (code "66") (name "Net-(D30-PadA)") (class "Default")
      (node (ref "D30") (pin "A") (pinfunction "A_A") (pintype "passive"))
      (node (ref "F8") (pin "2") (pinfunction "2_2") (pintype "passive"))
      (node (ref "F8") (pin "4") (pinfunction "2_4") (pintype "passive"))
      (node (ref "IC8") (pin "3") (pinfunction "I-_3") (pintype "bidirectional"))
      (node (ref "IC8") (pin "4") (pinfunction "I-_4") (pintype "bidirectional"))
    )
    (net (code "67") (name "Net-(D31-PadA)") (class "Default")
      (node (ref "D31") (pin "A") (pinfunction "A_A") (pintype "passive"))
      (node (ref "D32") (pin "C") (pinfunction "C_C") (pintype "passive"))
      (node (ref "IC8") (pin "1") (pinfunction "I+_1") (pintype "bidirectional"))
      (node (ref "IC8") (pin "2") (pinfunction "I+_2") (pintype "bidirectional"))
      (node (ref "R53") (pin "2") (pinfunction "2_2") (pintype "passive"))
      (node (ref "X15") (pin "1") (pinfunction "PIN_1") (pintype "bidirectional"))
      (node (ref "X15") (pin "2") (pinfunction "PIN_2") (pintype "bidirectional"))
      (node (ref "X15") (pin "3") (pinfunction "PIN_3") (pintype "bidirectional"))
      (node (ref "X15") (pin "4") (pinfunction "PIN_4") (pintype "bidirectional"))
      (node (ref "X15") (pin "5") (pinfunction "PIN_5") (pintype "bidirectional"))
      (node (ref "X15") (pin "6") (pinfunction "PIN_6") (pintype "bidirectional"))
    )
    (net (code "68") (name "Net-(D31-PadC)") (class "Default")
      (node (ref "D31") (pin "C") (pinfunction "C_C") (pintype "passive"))
      (node (ref "R54") (pin "2") (pinfunction "2_2") (pintype "passive"))
    )
    (net (code "69") (name "Net-(D32-PadA)") (class "Default")
      (node (ref "D32") (pin "A") (pinfunction "A_A") (pintype "passive"))
      (node (ref "Q16") (pin "5") (pinfunction "D_5") (pintype "passive"))
      (node (ref "Q16") (pin "6") (pinfunction "D_6") (pintype "passive"))
      (node (ref "Q16") (pin "7") (pinfunction "D_7") (pintype "passive"))
      (node (ref "Q16") (pin "8") (pinfunction "D_8") (pintype "passive"))
      (node (ref "Q16") (pin "9") (pinfunction "D_9") (pintype "passive"))
      (node (ref "R54") (pin "1") (pinfunction "1_1") (pintype "passive"))
      (node (ref "X16") (pin "1") (pinfunction "PIN_1") (pintype "bidirectional"))
      (node (ref "X16") (pin "2") (pinfunction "PIN_2") (pintype "bidirectional"))
      (node (ref "X16") (pin "3") (pinfunction "PIN_3") (pintype "bidirectional"))
      (node (ref "X16") (pin "4") (pinfunction "PIN_4") (pintype "bidirectional"))
      (node (ref "X16") (pin "5") (pinfunction "PIN_5") (pintype "bidirectional"))
      (node (ref "X16") (pin "6") (pinfunction "PIN_6") (pintype "bidirectional"))
    )
    (net (code "70") (name "Net-(D35-PadA)") (class "Default")
      (node (ref "D35") (pin "A") (pinfunction "A_A") (pintype "passive"))
      (node (ref "R65") (pin "1") (pinfunction "1_1") (pintype "passive"))
    )
    (net (code "71") (name "Net-(D36-PadA)") (class "Default")
      (node (ref "D36") (pin "A") (pinfunction "A_A") (pintype "passive"))
      (node (ref "R66") (pin "1") (pinfunction "1_1") (pintype "passive"))
    )
    (net (code "72") (name "Net-(D37-PadA)") (class "Default")
      (node (ref "D37") (pin "A") (pinfunction "A_A") (pintype "passive"))
      (node (ref "R67") (pin "1") (pinfunction "1_1") (pintype "passive"))
    )
    (net (code "73") (name "Net-(D38-PadA)") (class "Default")
      (node (ref "D38") (pin "A") (pinfunction "A_A") (pintype "passive"))
      (node (ref "R68") (pin "1") (pinfunction "1_1") (pintype "passive"))
    )
    (net (code "74") (name "Net-(IC1-FILTER)") (class "Default")
      (node (ref "C1") (pin "1") (pinfunction "1_1") (pintype "passive"))
      (node (ref "IC1") (pin "6") (pinfunction "FILTER_6") (pintype "bidirectional"))
    )
    (net (code "75") (name "Net-(IC2-FILTER)") (class "Default")
      (node (ref "C3") (pin "1") (pinfunction "1_1") (pintype "passive"))
      (node (ref "IC2") (pin "6") (pinfunction "FILTER_6") (pintype "bidirectional"))
    )
    (net (code "76") (name "Net-(IC3-FILTER)") (class "Default")
      (node (ref "C5") (pin "1") (pinfunction "1_1") (pintype "passive"))
      (node (ref "IC3") (pin "6") (pinfunction "FILTER_6") (pintype "bidirectional"))
    )
    (net (code "77") (name "Net-(IC4-FILTER)") (class "Default")
      (node (ref "C7") (pin "1") (pinfunction "1_1") (pintype "passive"))
      (node (ref "IC4") (pin "6") (pinfunction "FILTER_6") (pintype "bidirectional"))
    )
    (net (code "78") (name "Net-(IC5-FILTER)") (class "Default")
      (node (ref "C9") (pin "1") (pinfunction "1_1") (pintype "passive"))
      (node (ref "IC5") (pin "6") (pinfunction "FILTER_6") (pintype "bidirectional"))
    )
    (net (code "79") (name "Net-(IC6-FILTER)") (class "Default")
      (node (ref "C11") (pin "1") (pinfunction "1_1") (pintype "passive"))
      (node (ref "IC6") (pin "6") (pinfunction "FILTER_6") (pintype "bidirectional"))
    )
    (net (code "80") (name "Net-(IC7-FILTER)") (class "Default")
      (node (ref "C13") (pin "1") (pinfunction "1_1") (pintype "passive"))
      (node (ref "IC7") (pin "6") (pinfunction "FILTER_6") (pintype "bidirectional"))
    )
    (net (code "81") (name "Net-(IC8-FILTER)") (class "Default")
      (node (ref "C15") (pin "1") (pinfunction "1_1") (pintype "passive"))
      (node (ref "IC8") (pin "6") (pinfunction "FILTER_6") (pintype "bidirectional"))
    )
    (net (code "82") (name "Net-(IC9-PB6(XTAL1{slash}TOSC1))") (class "Default")
      (node (ref "C19") (pin "1") (pinfunction "1_1") (pintype "passive"))
      (node (ref "IC9") (pin "7") (pinfunction "PB6(XTAL1/TOSC1)_7") (pintype "bidirectional"))
      (node (ref "XTAL1") (pin "1") (pinfunction "1_1") (pintype "passive"))
    )
    (net (code "83") (name "Net-(IC9-PB7(XTAL2{slash}TOSC2))") (class "Default")
      (node (ref "C20") (pin "1") (pinfunction "1_1") (pintype "passive"))
      (node (ref "IC9") (pin "8") (pinfunction "PB7(XTAL2/TOSC2)_8") (pintype "bidirectional"))
      (node (ref "XTAL1") (pin "3") (pinfunction "3_3") (pintype "passive"))
    )
    (net (code "84") (name "Net-(IC10-CB)") (class "Default")
      (node (ref "C23") (pin "1") (pinfunction "1_1") (pintype "passive"))
      (node (ref "IC10") (pin "1") (pinfunction "CB_1") (pintype "bidirectional"))
    )
    (net (code "85") (name "Net-(IC10-FB)") (class "Default")
      (node (ref "IC10") (pin "3") (pinfunction "FB_3") (pintype "bidirectional"))
      (node (ref "R60") (pin "1") (pinfunction "1_1") (pintype "passive"))
      (node (ref "R61") (pin "2") (pinfunction "2_2") (pintype "passive"))
    )
    (net (code "86") (name "Net-(IC10-SW)") (class "Default")
      (node (ref "C23") (pin "2") (pinfunction "2_2") (pintype "passive"))
      (node (ref "IC10") (pin "6") (pinfunction "SW_6") (pintype "bidirectional"))
      (node (ref "L1") (pin "1") (pinfunction "1_1") (pintype "passive"))
    )
    (net (code "87") (name "Net-(IC11-A0)") (class "Default")
      (node (ref "IC11") (pin "5") (pinfunction "A0_5") (pintype "bidirectional"))
      (node (ref "R62") (pin "1") (pinfunction "1_1") (pintype "passive"))
    )
    (net (code "88") (name "Net-(IC11-INT)") (class "Default")
      (node (ref "D33") (pin "A") (pinfunction "A_A") (pintype "passive"))
      (node (ref "IC11") (pin "8") (pinfunction "INT_8") (pintype "bidirectional"))
    )
    (net (code "89") (name "Net-(IC15-A0)") (class "Default")
      (node (ref "IC15") (pin "5") (pinfunction "A0_5") (pintype "bidirectional"))
      (node (ref "R64") (pin "1") (pinfunction "1_1") (pintype "passive"))
    )
    (net (code "90") (name "Net-(IC15-A1)") (class "Default")
      (node (ref "IC15") (pin "4") (pinfunction "A1_4") (pintype "bidirectional"))
      (node (ref "R63") (pin "1") (pinfunction "1_1") (pintype "passive"))
    )
    (net (code "91") (name "Net-(IC15-GPIO0)") (class "Default")
      (node (ref "IC15") (pin "10") (pinfunction "GPIO0_10") (pintype "bidirectional"))
      (node (ref "S10") (pin "1") (pinfunction "1_1") (pintype "passive"))
    )
    (net (code "92") (name "Net-(IC15-GPIO1)") (class "Default")
      (node (ref "IC15") (pin "11") (pinfunction "GPIO1_11") (pintype "bidirectional"))
      (node (ref "S10") (pin "2") (pinfunction "2_2") (pintype "passive"))
    )
    (net (code "93") (name "Net-(IC15-GPIO2)") (class "Default")
      (node (ref "IC15") (pin "12") (pinfunction "GPIO2_12") (pintype "bidirectional"))
      (node (ref "S10") (pin "3") (pinfunction "3_3") (pintype "passive"))
    )
    (net (code "94") (name "Net-(IC15-GPIO3)") (class "Default")
      (node (ref "IC15") (pin "13") (pinfunction "GPIO3_13") (pintype "bidirectional"))
      (node (ref "S10") (pin "4") (pinfunction "4_4") (pintype "passive"))
    )
    (net (code "95") (name "Net-(IC15-GPIO4)") (class "Default")
      (node (ref "IC15") (pin "14") (pinfunction "GPIO4_14") (pintype "bidirectional"))
      (node (ref "S10") (pin "5") (pinfunction "5_5") (pintype "passive"))
    )
    (net (code "96") (name "Net-(IC15-GPIO5)") (class "Default")
      (node (ref "IC15") (pin "15") (pinfunction "GPIO5_15") (pintype "bidirectional"))
      (node (ref "S10") (pin "6") (pinfunction "6_6") (pintype "passive"))
    )
    (net (code "97") (name "Net-(IC15-GPIO6)") (class "Default")
      (node (ref "IC15") (pin "16") (pinfunction "GPIO6_16") (pintype "bidirectional"))
      (node (ref "S10") (pin "7") (pinfunction "7_7") (pintype "passive"))
    )
    (net (code "98") (name "Net-(IC15-GPIO7)") (class "Default")
      (node (ref "IC15") (pin "17") (pinfunction "GPIO7_17") (pintype "bidirectional"))
      (node (ref "S10") (pin "8") (pinfunction "8_8") (pintype "passive"))
    )
    (net (code "99") (name "Net-(IC15-INT)") (class "Default")
      (node (ref "D34") (pin "A") (pinfunction "A_A") (pintype "passive"))
      (node (ref "IC15") (pin "8") (pinfunction "INT_8") (pintype "bidirectional"))
    )
    (net (code "100") (name "Net-(IC16-OSC1)") (class "Default")
      (node (ref "C33") (pin "2") (pinfunction "2_2") (pintype "passive"))
      (node (ref "IC16") (pin "6") (pinfunction "OSC1_6") (pintype "bidirectional"))
      (node (ref "XTAL2") (pin "3") (pinfunction "3_3") (pintype "passive"))
    )
    (net (code "101") (name "Net-(IC16-OSC2)") (class "Default")
      (node (ref "C32") (pin "2") (pinfunction "2_2") (pintype "passive"))
      (node (ref "IC16") (pin "5") (pinfunction "OSC2_5") (pintype "bidirectional"))
      (node (ref "XTAL2") (pin "1") (pinfunction "1_1") (pintype "passive"))
    )
    (net (code "102") (name "Net-(IC16-RXCAN)") (class "Default")
      (node (ref "D38") (pin "C") (pinfunction "C_C") (pintype "passive"))
      (node (ref "IC16") (pin "2") (pinfunction "RXCAN_2") (pintype "bidirectional"))
      (node (ref "IC17") (pin "4") (pinfunction "RXD_4") (pintype "bidirectional"))
    )
    (net (code "103") (name "Net-(IC16-TXCAN)") (class "Default")
      (node (ref "D37") (pin "C") (pinfunction "C_C") (pintype "passive"))
      (node (ref "IC16") (pin "1") (pinfunction "TXCAN_1") (pintype "bidirectional"))
      (node (ref "IC17") (pin "1") (pinfunction "TXD_1") (pintype "bidirectional"))
    )
    (net (code "104") (name "Net-(IC17-CANH)") (class "Default")
      (node (ref "IC17") (pin "7") (pinfunction "CANH_7") (pintype "bidirectional"))
      (node (ref "JP1") (pin "1") (pinfunction "1_1") (pintype "passive"))
      (node (ref "X3") (pin "2") (pinfunction "2_2") (pintype "passive"))
      (node (ref "X4") (pin "2") (pinfunction "2_2") (pintype "passive"))
    )
    (net (code "105") (name "Net-(IC17-CANL)") (class "Default")
      (node (ref "IC17") (pin "6") (pinfunction "CANL_6") (pintype "bidirectional"))
      (node (ref "R69") (pin "1") (pinfunction "1_1") (pintype "passive"))
      (node (ref "X3") (pin "3") (pinfunction "3_3") (pintype "passive"))
      (node (ref "X4") (pin "3") (pinfunction "3_3") (pintype "passive"))
    )
    (net (code "106") (name "Net-(JP1-Pad2)") (class "Default")
      (node (ref "JP1") (pin "2") (pinfunction "2_2") (pintype "passive"))
      (node (ref "R69") (pin "2") (pinfunction "2_2") (pintype "passive"))
    )
    (net (code "107") (name "Net-(OK1-A)") (class "Default")
      (node (ref "OK1") (pin "1") (pinfunction "A_1") (pintype "passive"))
      (node (ref "R2") (pin "2") (pinfunction "2_2") (pintype "passive"))
    )
    (net (code "108") (name "Net-(OK1-COL)") (class "Default")
      (node (ref "OK1") (pin "4") (pinfunction "COL_4") (pintype "passive"))
      (node (ref "R4") (pin "1") (pinfunction "1_1") (pintype "passive"))
    )
    (net (code "109") (name "Net-(OK1-EMIT)") (class "Default")
      (node (ref "OK1") (pin "3") (pinfunction "EMIT_3") (pintype "passive"))
      (node (ref "Q1") (pin "3") (pinfunction "G_3") (pintype "passive"))
      (node (ref "Q1") (pin "4") (pinfunction "G_4") (pintype "passive"))
      (node (ref "R1") (pin "2") (pinfunction "2_2") (pintype "passive"))
    )
    (net (code "110") (name "Net-(OK2-A)") (class "Default")
      (node (ref "OK2") (pin "1") (pinfunction "A_1") (pintype "passive"))
      (node (ref "R9") (pin "2") (pinfunction "2_2") (pintype "passive"))
    )
    (net (code "111") (name "Net-(OK2-COL)") (class "Default")
      (node (ref "OK2") (pin "4") (pinfunction "COL_4") (pintype "passive"))
      (node (ref "R11") (pin "1") (pinfunction "1_1") (pintype "passive"))
    )
    (net (code "112") (name "Net-(OK2-EMIT)") (class "Default")
      (node (ref "OK2") (pin "3") (pinfunction "EMIT_3") (pintype "passive"))
      (node (ref "Q3") (pin "3") (pinfunction "G_3") (pintype "passive"))
      (node (ref "Q3") (pin "4") (pinfunction "G_4") (pintype "passive"))
      (node (ref "R8") (pin "2") (pinfunction "2_2") (pintype "passive"))
    )
    (net (code "113") (name "Net-(OK3-A)") (class "Default")
      (node (ref "OK3") (pin "1") (pinfunction "A_1") (pintype "passive"))
      (node (ref "R16") (pin "2") (pinfunction "2_2") (pintype "passive"))
    )
    (net (code "114") (name "Net-(OK3-COL)") (class "Default")
      (node (ref "OK3") (pin "4") (pinfunction "COL_4") (pintype "passive"))
      (node (ref "R18") (pin "1") (pinfunction "1_1") (pintype "passive"))
    )
    (net (code "115") (name "Net-(OK3-EMIT)") (class "Default")
      (node (ref "OK3") (pin "3") (pinfunction "EMIT_3") (pintype "passive"))
      (node (ref "Q5") (pin "3") (pinfunction "G_3") (pintype "passive"))
      (node (ref "Q5") (pin "4") (pinfunction "G_4") (pintype "passive"))
      (node (ref "R15") (pin "2") (pinfunction "2_2") (pintype "passive"))
    )
    (net (code "116") (name "Net-(OK4-A)") (class "Default")
      (node (ref "OK4") (pin "1") (pinfunction "A_1") (pintype "passive"))
      (node (ref "R23") (pin "2") (pinfunction "2_2") (pintype "passive"))
    )
    (net (code "117") (name "Net-(OK4-COL)") (class "Default")
      (node (ref "OK4") (pin "4") (pinfunction "COL_4") (pintype "passive"))
      (node (ref "R25") (pin "1") (pinfunction "1_1") (pintype "passive"))
    )
    (net (code "118") (name "Net-(OK4-EMIT)") (class "Default")
      (node (ref "OK4") (pin "3") (pinfunction "EMIT_3") (pintype "passive"))
      (node (ref "Q7") (pin "3") (pinfunction "G_3") (pintype "passive"))
      (node (ref "Q7") (pin "4") (pinfunction "G_4") (pintype "passive"))
      (node (ref "R22") (pin "2") (pinfunction "2_2") (pintype "passive"))
    )
    (net (code "119") (name "Net-(OK5-A)") (class "Default")
      (node (ref "OK5") (pin "1") (pinfunction "A_1") (pintype "passive"))
      (node (ref "R35") (pin "2") (pinfunction "2_2") (pintype "passive"))
    )
    (net (code "120") (name "Net-(OK5-COL)") (class "Default")
      (node (ref "OK5") (pin "4") (pinfunction "COL_4") (pintype "passive"))
      (node (ref "R32") (pin "1") (pinfunction "1_1") (pintype "passive"))
    )
    (net (code "121") (name "Net-(OK5-EMIT)") (class "Default")
      (node (ref "OK5") (pin "3") (pinfunction "EMIT_3") (pintype "passive"))
      (node (ref "Q10") (pin "3") (pinfunction "G_3") (pintype "passive"))
      (node (ref "Q10") (pin "4") (pinfunction "G_4") (pintype "passive"))
      (node (ref "R34") (pin "2") (pinfunction "2_2") (pintype "passive"))
    )
    (net (code "122") (name "Net-(OK6-A)") (class "Default")
      (node (ref "OK6") (pin "1") (pinfunction "A_1") (pintype "passive"))
      (node (ref "R42") (pin "2") (pinfunction "2_2") (pintype "passive"))
    )
    (net (code "123") (name "Net-(OK6-COL)") (class "Default")
      (node (ref "OK6") (pin "4") (pinfunction "COL_4") (pintype "passive"))
      (node (ref "R39") (pin "1") (pinfunction "1_1") (pintype "passive"))
    )
    (net (code "124") (name "Net-(OK6-EMIT)") (class "Default")
      (node (ref "OK6") (pin "3") (pinfunction "EMIT_3") (pintype "passive"))
      (node (ref "Q12") (pin "3") (pinfunction "G_3") (pintype "passive"))
      (node (ref "Q12") (pin "4") (pinfunction "G_4") (pintype "passive"))
      (node (ref "R41") (pin "2") (pinfunction "2_2") (pintype "passive"))
    )
    (net (code "125") (name "Net-(OK7-A)") (class "Default")
      (node (ref "OK7") (pin "1") (pinfunction "A_1") (pintype "passive"))
      (node (ref "R49") (pin "2") (pinfunction "2_2") (pintype "passive"))
    )
    (net (code "126") (name "Net-(OK7-COL)") (class "Default")
      (node (ref "OK7") (pin "4") (pinfunction "COL_4") (pintype "passive"))
      (node (ref "R46") (pin "1") (pinfunction "1_1") (pintype "passive"))
    )
    (net (code "127") (name "Net-(OK7-EMIT)") (class "Default")
      (node (ref "OK7") (pin "3") (pinfunction "EMIT_3") (pintype "passive"))
      (node (ref "Q14") (pin "3") (pinfunction "G_3") (pintype "passive"))
      (node (ref "Q14") (pin "4") (pinfunction "G_4") (pintype "passive"))
      (node (ref "R48") (pin "2") (pinfunction "2_2") (pintype "passive"))
    )
    (net (code "128") (name "Net-(OK8-A)") (class "Default")
      (node (ref "OK8") (pin "1") (pinfunction "A_1") (pintype "passive"))
      (node (ref "R56") (pin "2") (pinfunction "2_2") (pintype "passive"))
    )
    (net (code "129") (name "Net-(OK8-COL)") (class "Default")
      (node (ref "OK8") (pin "4") (pinfunction "COL_4") (pintype "passive"))
      (node (ref "R53") (pin "1") (pinfunction "1_1") (pintype "passive"))
    )
    (net (code "130") (name "Net-(OK8-EMIT)") (class "Default")
      (node (ref "OK8") (pin "3") (pinfunction "EMIT_3") (pintype "passive"))
      (node (ref "Q16") (pin "3") (pinfunction "G_3") (pintype "passive"))
      (node (ref "Q16") (pin "4") (pinfunction "G_4") (pintype "passive"))
      (node (ref "R55") (pin "2") (pinfunction "2_2") (pintype "passive"))
    )
    (net (code "131") (name "Net-(Q2-B)") (class "Default")
      (node (ref "D3") (pin "C") (pinfunction "C_C") (pintype "passive"))
      (node (ref "Q2") (pin "3") (pinfunction "B_3") (pintype "passive"))
      (node (ref "R5") (pin "2") (pinfunction "2_2") (pintype "passive"))
    )
    (net (code "132") (name "Net-(Q2-C)") (class "Default")
      (node (ref "Q2") (pin "1") (pinfunction "C_1") (pintype "passive"))
      (node (ref "R7") (pin "2") (pinfunction "2_2") (pintype "passive"))
    )
    (net (code "133") (name "Net-(Q2-E)") (class "Default")
      (node (ref "D4") (pin "C") (pinfunction "C_C") (pintype "passive"))
      (node (ref "Q2") (pin "2") (pinfunction "E_2") (pintype "passive"))
    )
    (net (code "134") (name "Net-(Q4-B)") (class "Default")
      (node (ref "D7") (pin "C") (pinfunction "C_C") (pintype "passive"))
      (node (ref "Q4") (pin "3") (pinfunction "B_3") (pintype "passive"))
      (node (ref "R12") (pin "2") (pinfunction "2_2") (pintype "passive"))
    )
    (net (code "135") (name "Net-(Q4-C)") (class "Default")
      (node (ref "Q4") (pin "1") (pinfunction "C_1") (pintype "passive"))
      (node (ref "R14") (pin "2") (pinfunction "2_2") (pintype "passive"))
    )
    (net (code "136") (name "Net-(Q4-E)") (class "Default")
      (node (ref "D8") (pin "C") (pinfunction "C_C") (pintype "passive"))
      (node (ref "Q4") (pin "2") (pinfunction "E_2") (pintype "passive"))
    )
    (net (code "137") (name "Net-(Q6-B)") (class "Default")
      (node (ref "D11") (pin "C") (pinfunction "C_C") (pintype "passive"))
      (node (ref "Q6") (pin "3") (pinfunction "B_3") (pintype "passive"))
      (node (ref "R19") (pin "2") (pinfunction "2_2") (pintype "passive"))
    )
    (net (code "138") (name "Net-(Q6-C)") (class "Default")
      (node (ref "Q6") (pin "1") (pinfunction "C_1") (pintype "passive"))
      (node (ref "R21") (pin "2") (pinfunction "2_2") (pintype "passive"))
    )
    (net (code "139") (name "Net-(Q6-E)") (class "Default")
      (node (ref "D12") (pin "C") (pinfunction "C_C") (pintype "passive"))
      (node (ref "Q6") (pin "2") (pinfunction "E_2") (pintype "passive"))
    )
    (net (code "140") (name "Net-(Q8-B)") (class "Default")
      (node (ref "D15") (pin "C") (pinfunction "C_C") (pintype "passive"))
      (node (ref "Q8") (pin "3") (pinfunction "B_3") (pintype "passive"))
      (node (ref "R26") (pin "2") (pinfunction "2_2") (pintype "passive"))
    )
    (net (code "141") (name "Net-(Q8-C)") (class "Default")
      (node (ref "Q8") (pin "1") (pinfunction "C_1") (pintype "passive"))
      (node (ref "R28") (pin "2") (pinfunction "2_2") (pintype "passive"))
    )
    (net (code "142") (name "Net-(Q8-E)") (class "Default")
      (node (ref "D16") (pin "C") (pinfunction "C_C") (pintype "passive"))
      (node (ref "Q8") (pin "2") (pinfunction "E_2") (pintype "passive"))
    )
    (net (code "143") (name "Net-(Q9-B)") (class "Default")
      (node (ref "D18") (pin "C") (pinfunction "C_C") (pintype "passive"))
      (node (ref "Q9") (pin "3") (pinfunction "B_3") (pintype "passive"))
      (node (ref "R31") (pin "2") (pinfunction "2_2") (pintype "passive"))
    )
    (net (code "144") (name "Net-(Q9-C)") (class "Default")
      (node (ref "Q9") (pin "1") (pinfunction "C_1") (pintype "passive"))
      (node (ref "R29") (pin "2") (pinfunction "2_2") (pintype "passive"))
    )
    (net (code "145") (name "Net-(Q9-E)") (class "Default")
      (node (ref "D17") (pin "C") (pinfunction "C_C") (pintype "passive"))
      (node (ref "Q9") (pin "2") (pinfunction "E_2") (pintype "passive"))
    )
    (net (code "146") (name "Net-(Q11-B)") (class "Default")
      (node (ref "D22") (pin "C") (pinfunction "C_C") (pintype "passive"))
      (node (ref "Q11") (pin "3") (pinfunction "B_3") (pintype "passive"))
      (node (ref "R38") (pin "2") (pinfunction "2_2") (pintype "passive"))
    )
    (net (code "147") (name "Net-(Q11-C)") (class "Default")
      (node (ref "Q11") (pin "1") (pinfunction "C_1") (pintype "passive"))
      (node (ref "R36") (pin "2") (pinfunction "2_2") (pintype "passive"))
    )
    (net (code "148") (name "Net-(Q11-E)") (class "Default")
      (node (ref "D21") (pin "C") (pinfunction "C_C") (pintype "passive"))
      (node (ref "Q11") (pin "2") (pinfunction "E_2") (pintype "passive"))
    )
    (net (code "149") (name "Net-(Q13-B)") (class "Default")
      (node (ref "D26") (pin "C") (pinfunction "C_C") (pintype "passive"))
      (node (ref "Q13") (pin "3") (pinfunction "B_3") (pintype "passive"))
      (node (ref "R45") (pin "2") (pinfunction "2_2") (pintype "passive"))
    )
    (net (code "150") (name "Net-(Q13-C)") (class "Default")
      (node (ref "Q13") (pin "1") (pinfunction "C_1") (pintype "passive"))
      (node (ref "R43") (pin "2") (pinfunction "2_2") (pintype "passive"))
    )
    (net (code "151") (name "Net-(Q13-E)") (class "Default")
      (node (ref "D25") (pin "C") (pinfunction "C_C") (pintype "passive"))
      (node (ref "Q13") (pin "2") (pinfunction "E_2") (pintype "passive"))
    )
    (net (code "152") (name "Net-(Q15-B)") (class "Default")
      (node (ref "D30") (pin "C") (pinfunction "C_C") (pintype "passive"))
      (node (ref "Q15") (pin "3") (pinfunction "B_3") (pintype "passive"))
      (node (ref "R52") (pin "2") (pinfunction "2_2") (pintype "passive"))
    )
    (net (code "153") (name "Net-(Q15-C)") (class "Default")
      (node (ref "Q15") (pin "1") (pinfunction "C_1") (pintype "passive"))
      (node (ref "R50") (pin "2") (pinfunction "2_2") (pintype "passive"))
    )
    (net (code "154") (name "Net-(Q15-E)") (class "Default")
      (node (ref "D29") (pin "C") (pinfunction "C_C") (pintype "passive"))
      (node (ref "Q15") (pin "2") (pinfunction "E_2") (pintype "passive"))
    )
    (net (code "155") (name "RESET") (class "Default")
      (node (ref "C21") (pin "2") (pinfunction "2_2") (pintype "passive"))
      (node (ref "IC11") (pin "6") (pinfunction "RESET_6") (pintype "bidirectional"))
      (node (ref "IC14") (pin "6") (pinfunction "RESET_6") (pintype "bidirectional"))
      (node (ref "IC15") (pin "6") (pinfunction "RESET_6") (pintype "bidirectional"))
      (node (ref "IC9") (pin "29") (pinfunction "PC6(/RESET)_29") (pintype "bidirectional"))
      (node (ref "R57") (pin "1") (pinfunction "1_1") (pintype "passive"))
      (node (ref "S9") (pin "B1") (pinfunction "2_B1") (pintype "passive"))
      (node (ref "S9") (pin "B2") (pinfunction "2_B2") (pintype "passive"))
      (node (ref "X2") (pin "5") (pinfunction "5_5") (pintype "passive"))
    )
    (net (code "156") (name "SPI_CLK") (class "Default")
      (node (ref "IC16") (pin "10") (pinfunction "SCK_10") (pintype "bidirectional"))
      (node (ref "IC9") (pin "17") (pinfunction "PB5(SCK)_17") (pintype "bidirectional"))
      (node (ref "X2") (pin "3") (pinfunction "3_3") (pintype "passive"))
    )
    (net (code "157") (name "SPI_CS_CAN") (class "Default")
      (node (ref "IC16") (pin "13") (pinfunction "CS_13") (pintype "bidirectional"))
      (node (ref "IC9") (pin "14") (pinfunction "PB2(SS/OC1B)_14") (pintype "bidirectional"))
    )
    (net (code "158") (name "SPI_MISO") (class "Default")
      (node (ref "IC16") (pin "12") (pinfunction "SDO_12") (pintype "bidirectional"))
      (node (ref "IC9") (pin "16") (pinfunction "PB4(MISO)_16") (pintype "bidirectional"))
      (node (ref "X2") (pin "1") (pinfunction "1_1") (pintype "passive"))
    )
    (net (code "159") (name "SPI_MOSI") (class "Default")
      (node (ref "IC16") (pin "11") (pinfunction "SDI_11") (pintype "bidirectional"))
      (node (ref "IC9") (pin "15") (pinfunction "PB3(MOSI/OC2)_15") (pintype "bidirectional"))
      (node (ref "X2") (pin "4") (pinfunction "4_4") (pintype "passive"))
    )
    (net (code "160") (name "SW_1") (class "Default")
      (node (ref "IC11") (pin "17") (pinfunction "GPIO7_17") (pintype "bidirectional"))
      (node (ref "S1") (pin "B1") (pinfunction "2_B1") (pintype "passive"))
      (node (ref "S1") (pin "B2") (pinfunction "2_B2") (pintype "passive"))
    )
    (net (code "161") (name "SW_2") (class "Default")
      (node (ref "IC11") (pin "16") (pinfunction "GPIO6_16") (pintype "bidirectional"))
      (node (ref "S2") (pin "B1") (pinfunction "2_B1") (pintype "passive"))
      (node (ref "S2") (pin "B2") (pinfunction "2_B2") (pintype "passive"))
    )
    (net (code "162") (name "SW_3") (class "Default")
      (node (ref "IC11") (pin "15") (pinfunction "GPIO5_15") (pintype "bidirectional"))
      (node (ref "S3") (pin "B1") (pinfunction "2_B1") (pintype "passive"))
      (node (ref "S3") (pin "B2") (pinfunction "2_B2") (pintype "passive"))
    )
    (net (code "163") (name "SW_4") (class "Default")
      (node (ref "IC11") (pin "14") (pinfunction "GPIO4_14") (pintype "bidirectional"))
      (node (ref "S4") (pin "B1") (pinfunction "2_B1") (pintype "passive"))
      (node (ref "S4") (pin "B2") (pinfunction "2_B2") (pintype "passive"))
    )
    (net (code "164") (name "SW_5") (class "Default")
      (node (ref "IC11") (pin "13") (pinfunction "GPIO3_13") (pintype "bidirectional"))
      (node (ref "S5") (pin "B1") (pinfunction "2_B1") (pintype "passive"))
      (node (ref "S5") (pin "B2") (pinfunction "2_B2") (pintype "passive"))
    )
    (net (code "165") (name "SW_6") (class "Default")
      (node (ref "IC11") (pin "12") (pinfunction "GPIO2_12") (pintype "bidirectional"))
      (node (ref "S6") (pin "B1") (pinfunction "2_B1") (pintype "passive"))
      (node (ref "S6") (pin "B2") (pinfunction "2_B2") (pintype "passive"))
    )
    (net (code "166") (name "SW_7") (class "Default")
      (node (ref "IC11") (pin "11") (pinfunction "GPIO1_11") (pintype "bidirectional"))
      (node (ref "S7") (pin "B1") (pinfunction "2_B1") (pintype "passive"))
      (node (ref "S7") (pin "B2") (pinfunction "2_B2") (pintype "passive"))
    )
    (net (code "167") (name "SW_8") (class "Default")
      (node (ref "IC11") (pin "10") (pinfunction "GPIO0_10") (pintype "bidirectional"))
      (node (ref "S8") (pin "B1") (pinfunction "2_B1") (pintype "passive"))
      (node (ref "S8") (pin "B2") (pinfunction "2_B2") (pintype "passive"))
    )
    (net (code "168") (name "UART_RX") (class "Default")
      (node (ref "IC9") (pin "30") (pinfunction "PD0(RXD)_30") (pintype "bidirectional"))
      (node (ref "X1") (pin "4") (pinfunction "4_4") (pintype "passive"))
    )
    (net (code "169") (name "UART_TX") (class "Default")
      (node (ref "IC9") (pin "31") (pinfunction "PD1(TXD)_31") (pintype "bidirectional"))
      (node (ref "X1") (pin "5") (pinfunction "5_5") (pintype "passive"))
    )
    (net (code "170") (name "VCC") (class "Default")
      (node (ref "C10") (pin "1") (pinfunction "1_1") (pintype "passive"))
      (node (ref "C12") (pin "1") (pinfunction "1_1") (pintype "passive"))
      (node (ref "C14") (pin "1") (pinfunction "1_1") (pintype "passive"))
      (node (ref "C16") (pin "1") (pinfunction "1_1") (pintype "passive"))
      (node (ref "C17") (pin "1") (pinfunction "1_1") (pintype "passive"))
      (node (ref "C18") (pin "1") (pinfunction "1_1") (pintype "passive"))
      (node (ref "C2") (pin "1") (pinfunction "1_1") (pintype "passive"))
      (node (ref "C22") (pin "2") (pinfunction "2_2") (pintype "passive"))
      (node (ref "C26") (pin "2") (pinfunction "2_2") (pintype "passive"))
      (node (ref "C27") (pin "1") (pinfunction "1_1") (pintype "passive"))
      (node (ref "C28") (pin "1") (pinfunction "1_1") (pintype "passive"))
      (node (ref "C29") (pin "2") (pinfunction "2_2") (pintype "passive"))
      (node (ref "C30") (pin "2") (pinfunction "2_2") (pintype "passive"))
      (node (ref "C31") (pin "1") (pinfunction "1_1") (pintype "passive"))
      (node (ref "C34") (pin "1") (pinfunction "1_1") (pintype "passive"))
      (node (ref "C35") (pin "2") (pinfunction "2_2") (pintype "passive"))
      (node (ref "C4") (pin "1") (pinfunction "1_1") (pintype "passive"))
      (node (ref "C6") (pin "1") (pinfunction "1_1") (pintype "passive"))
      (node (ref "C8") (pin "1") (pinfunction "1_1") (pintype "passive"))
      (node (ref "IC1") (pin "8") (pinfunction "VCC_8") (pintype "bidirectional"))
      (node (ref "IC11") (pin "18") (pinfunction "VCC_18") (pintype "bidirectional"))
      (node (ref "IC12") (pin "16") (pinfunction "VCC_16") (pintype "bidirectional"))
      (node (ref "IC13") (pin "16") (pinfunction "VCC_16") (pintype "bidirectional"))
      (node (ref "IC14") (pin "18") (pinfunction "VCC_18") (pintype "bidirectional"))
      (node (ref "IC15") (pin "18") (pinfunction "VCC_18") (pintype "bidirectional"))
      (node (ref "IC16") (pin "14") (pinfunction "VCC_14") (pintype "bidirectional"))
      (node (ref "IC17") (pin "3") (pinfunction "VCC_3") (pintype "bidirectional"))
      (node (ref "IC17") (pin "5") (pinfunction "VIO_5") (pintype "bidirectional"))
      (node (ref "IC2") (pin "8") (pinfunction "VCC_8") (pintype "bidirectional"))
      (node (ref "IC3") (pin "8") (pinfunction "VCC_8") (pintype "bidirectional"))
      (node (ref "IC4") (pin "8") (pinfunction "VCC_8") (pintype "bidirectional"))
      (node (ref "IC5") (pin "8") (pinfunction "VCC_8") (pintype "bidirectional"))
      (node (ref "IC6") (pin "8") (pinfunction "VCC_8") (pintype "bidirectional"))
      (node (ref "IC7") (pin "8") (pinfunction "VCC_8") (pintype "bidirectional"))
      (node (ref "IC8") (pin "8") (pinfunction "VCC_8") (pintype "bidirectional"))
      (node (ref "IC9") (pin "18") (pinfunction "AVCC_18") (pintype "bidirectional"))
      (node (ref "IC9") (pin "20") (pinfunction "AREF_20") (pintype "bidirectional"))
      (node (ref "IC9") (pin "4") (pinfunction "VCC_4") (pintype "bidirectional"))
      (node (ref "IC9") (pin "6") (pinfunction "VCC_6") (pintype "bidirectional"))
      (node (ref "L1") (pin "2") (pinfunction "2_2") (pintype "passive"))
      (node (ref "R57") (pin "2") (pinfunction "2_2") (pintype "passive"))
      (node (ref "R58") (pin "2") (pinfunction "2_2") (pintype "passive"))
      (node (ref "R59") (pin "1") (pinfunction "1_1") (pintype "passive"))
      (node (ref "R60") (pin "2") (pinfunction "2_2") (pintype "passive"))
      (node (ref "R62") (pin "2") (pinfunction "2_2") (pintype "passive"))
      (node (ref "R63") (pin "2") (pinfunction "2_2") (pintype "passive"))
      (node (ref "R64") (pin "2") (pinfunction "2_2") (pintype "passive"))
      (node (ref "R65") (pin "2") (pinfunction "2_2") (pintype "passive"))
      (node (ref "R67") (pin "2") (pinfunction "2_2") (pintype "passive"))
      (node (ref "R68") (pin "2") (pinfunction "2_2") (pintype "passive"))
      (node (ref "X1") (pin "3") (pinfunction "3_3") (pintype "passive"))
      (node (ref "X2") (pin "2") (pinfunction "2_2") (pintype "passive"))
    )
    (net (code "171") (name "V_OUT_1") (class "Default")
      (node (ref "IC12") (pin "12") (pinfunction "X3_12") (pintype "bidirectional"))
      (node (ref "R5") (pin "1") (pinfunction "1_1") (pintype "passive"))
      (node (ref "R6") (pin "2") (pinfunction "2_2") (pintype "passive"))
    )
    (net (code "172") (name "V_OUT_2") (class "Default")
      (node (ref "IC12") (pin "14") (pinfunction "X1_14") (pintype "bidirectional"))
      (node (ref "R12") (pin "1") (pinfunction "1_1") (pintype "passive"))
      (node (ref "R13") (pin "2") (pinfunction "2_2") (pintype "passive"))
    )
    (net (code "173") (name "V_OUT_3") (class "Default")
      (node (ref "IC12") (pin "1") (pinfunction "X4_1") (pintype "bidirectional"))
      (node (ref "R19") (pin "1") (pinfunction "1_1") (pintype "passive"))
      (node (ref "R20") (pin "2") (pinfunction "2_2") (pintype "passive"))
    )
    (net (code "174") (name "V_OUT_4") (class "Default")
      (node (ref "IC12") (pin "4") (pinfunction "X7_4") (pintype "bidirectional"))
      (node (ref "R26") (pin "1") (pinfunction "1_1") (pintype "passive"))
      (node (ref "R27") (pin "2") (pinfunction "2_2") (pintype "passive"))
    )
    (net (code "175") (name "V_OUT_5") (class "Default")
      (node (ref "IC13") (pin "2") (pinfunction "X6_2") (pintype "bidirectional"))
      (node (ref "R30") (pin "2") (pinfunction "2_2") (pintype "passive"))
      (node (ref "R31") (pin "1") (pinfunction "1_1") (pintype "passive"))
    )
    (net (code "176") (name "V_OUT_6") (class "Default")
      (node (ref "IC13") (pin "5") (pinfunction "X5_5") (pintype "bidirectional"))
      (node (ref "R37") (pin "2") (pinfunction "2_2") (pintype "passive"))
      (node (ref "R38") (pin "1") (pinfunction "1_1") (pintype "passive"))
    )
    (net (code "177") (name "V_OUT_7") (class "Default")
      (node (ref "IC13") (pin "13") (pinfunction "X0_13") (pintype "bidirectional"))
      (node (ref "R44") (pin "2") (pinfunction "2_2") (pintype "passive"))
      (node (ref "R45") (pin "1") (pinfunction "1_1") (pintype "passive"))
    )
    (net (code "178") (name "V_OUT_8") (class "Default")
      (node (ref "IC13") (pin "15") (pinfunction "X2_15") (pintype "bidirectional"))
      (node (ref "R51") (pin "2") (pinfunction "2_2") (pintype "passive"))
      (node (ref "R52") (pin "1") (pinfunction "1_1") (pintype "passive"))
    )
    (net (code "179") (name "unconnected-(IC9-ADC6-Pad19)") (class "Default")
      (node (ref "IC9") (pin "19") (pinfunction "ADC6_19") (pintype "bidirectional"))
    )
    (net (code "180") (name "unconnected-(IC9-ADC7-Pad22)") (class "Default")
      (node (ref "IC9") (pin "22") (pinfunction "ADC7_22") (pintype "bidirectional"))
    )
    (net (code "181") (name "unconnected-(IC9-PB1(OC1A)-Pad13)") (class "Default")
      (node (ref "IC9") (pin "13") (pinfunction "PB1(OC1A)_13") (pintype "bidirectional"))
    )
    (net (code "182") (name "unconnected-(IC9-PC2(ADC2)-Pad25)") (class "Default")
      (node (ref "IC9") (pin "25") (pinfunction "PC2(ADC2)_25") (pintype "bidirectional"))
    )
    (net (code "183") (name "unconnected-(IC9-PC3(ADC3)-Pad26)") (class "Default")
      (node (ref "IC9") (pin "26") (pinfunction "PC3(ADC3)_26") (pintype "bidirectional"))
    )
    (net (code "184") (name "unconnected-(IC9-PD4(XCK{slash}T0)-Pad2)") (class "Default")
      (node (ref "IC9") (pin "2") (pinfunction "PD4(XCK/T0)_2") (pintype "bidirectional"))
    )
    (net (code "185") (name "unconnected-(IC12-INH-Pad6)") (class "Default")
      (node (ref "IC12") (pin "6") (pinfunction "INH_6") (pintype "input"))
    )
    (net (code "186") (name "unconnected-(IC13-INH-Pad6)") (class "Default")
      (node (ref "IC13") (pin "6") (pinfunction "INH_6") (pintype "input"))
    )
    (net (code "187") (name "unconnected-(IC14-INT-Pad8)") (class "Default")
      (node (ref "IC14") (pin "8") (pinfunction "INT_8") (pintype "bidirectional"))
    )
    (net (code "188") (name "unconnected-(IC16-CLKO{slash}SOF-Pad3)") (class "Default")
      (node (ref "IC16") (pin "3") (pinfunction "CLKO/SOF_3") (pintype "bidirectional"))
    )
    (net (code "189") (name "unconnected-(IC16-GPIO0-Pad9)") (class "Default")
      (node (ref "IC16") (pin "9") (pinfunction "GPIO0_9") (pintype "bidirectional"))
    )
    (net (code "190") (name "unconnected-(IC16-GPIO1-Pad8)") (class "Default")
      (node (ref "IC16") (pin "8") (pinfunction "GPIO1_8") (pintype "bidirectional"))
    )
  )
)
